# EasyEDA-Project.net
KiCad netlist of a schematic drawn in EasyEDA Pro
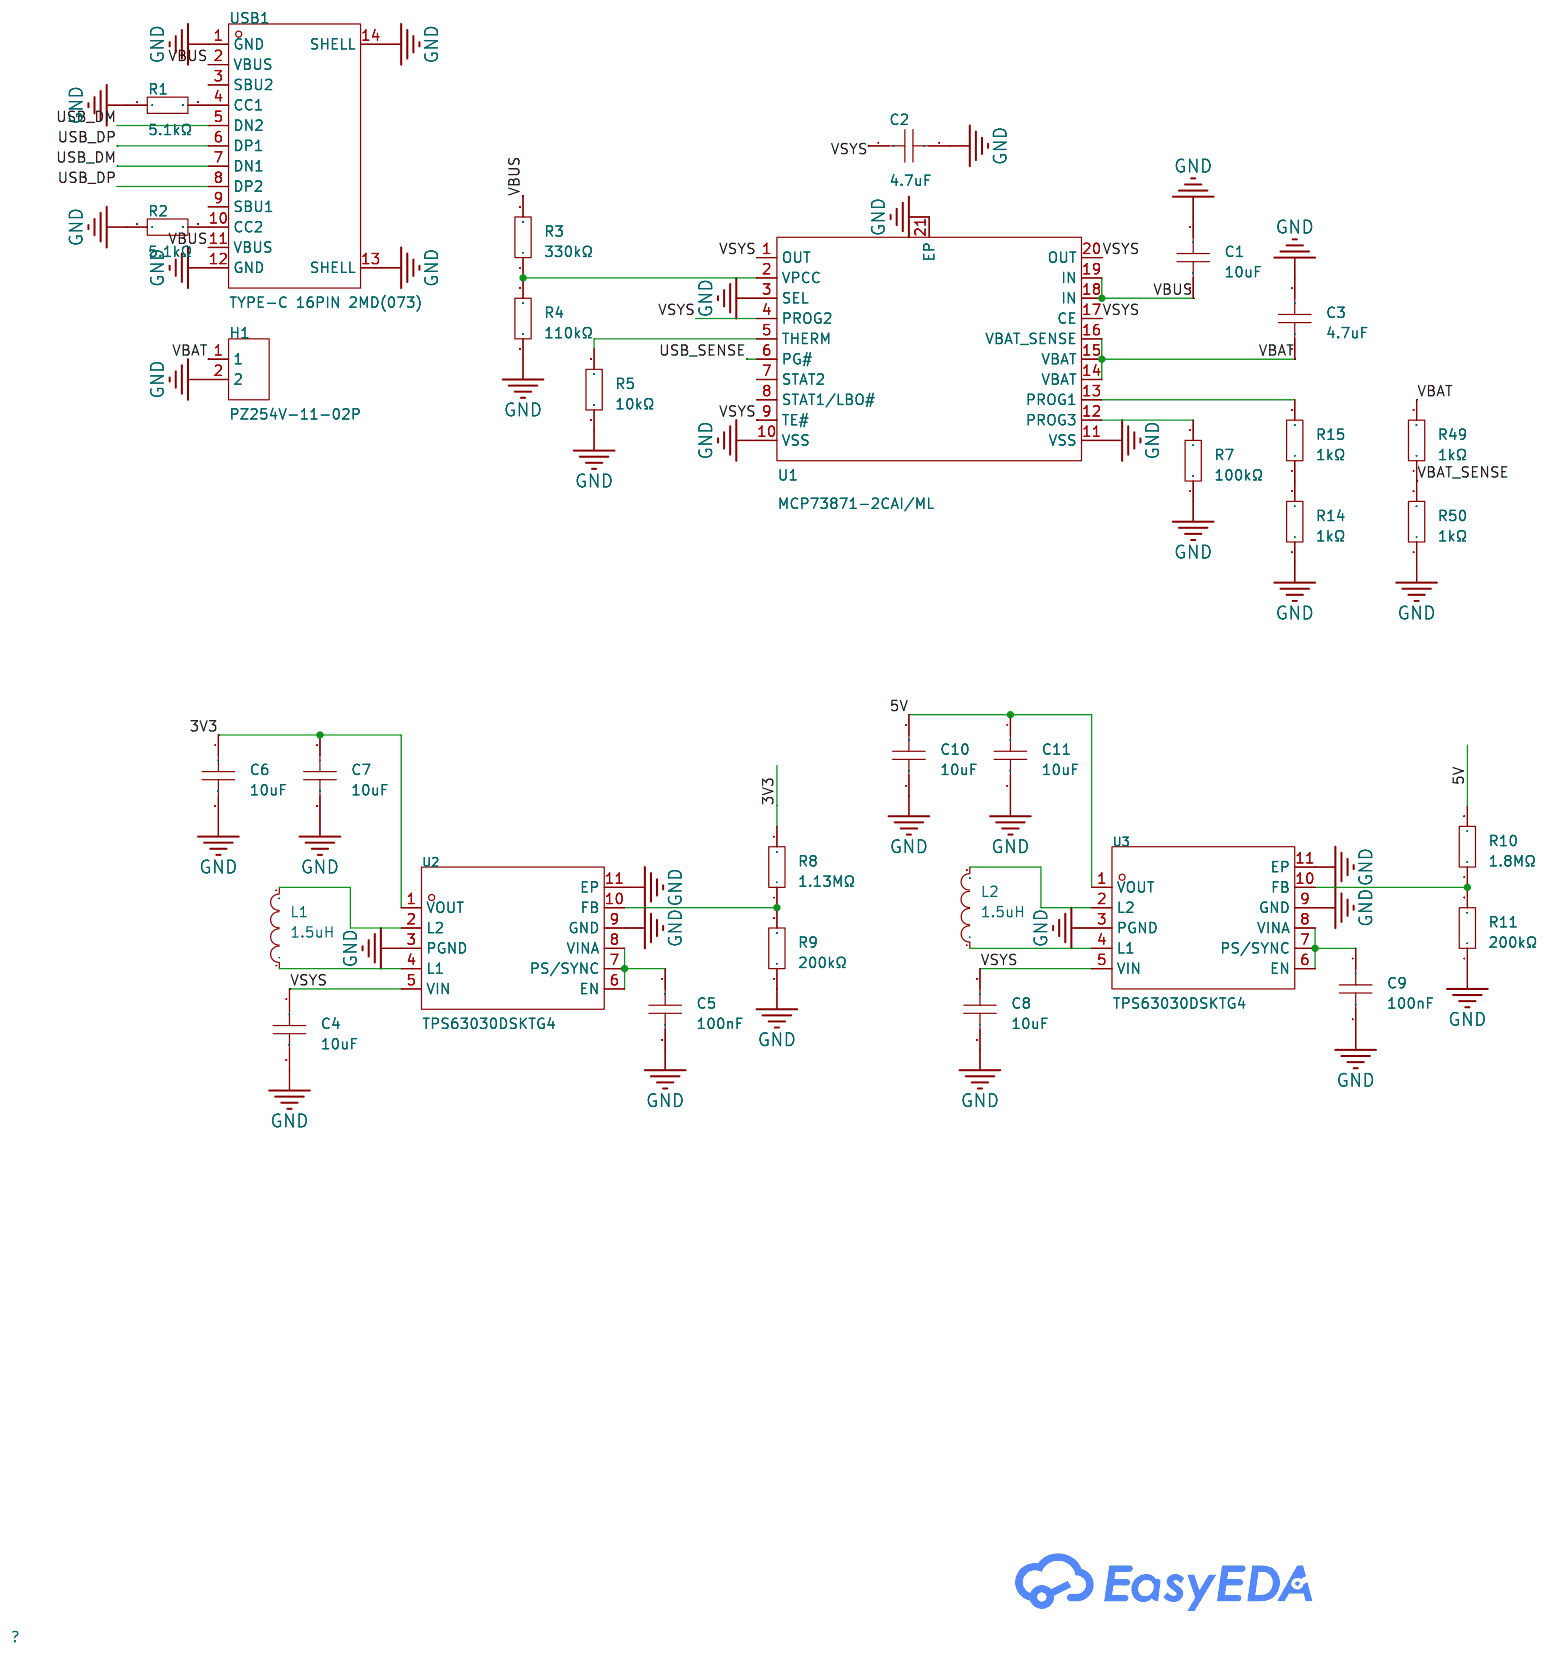
[diagram p0: Power]
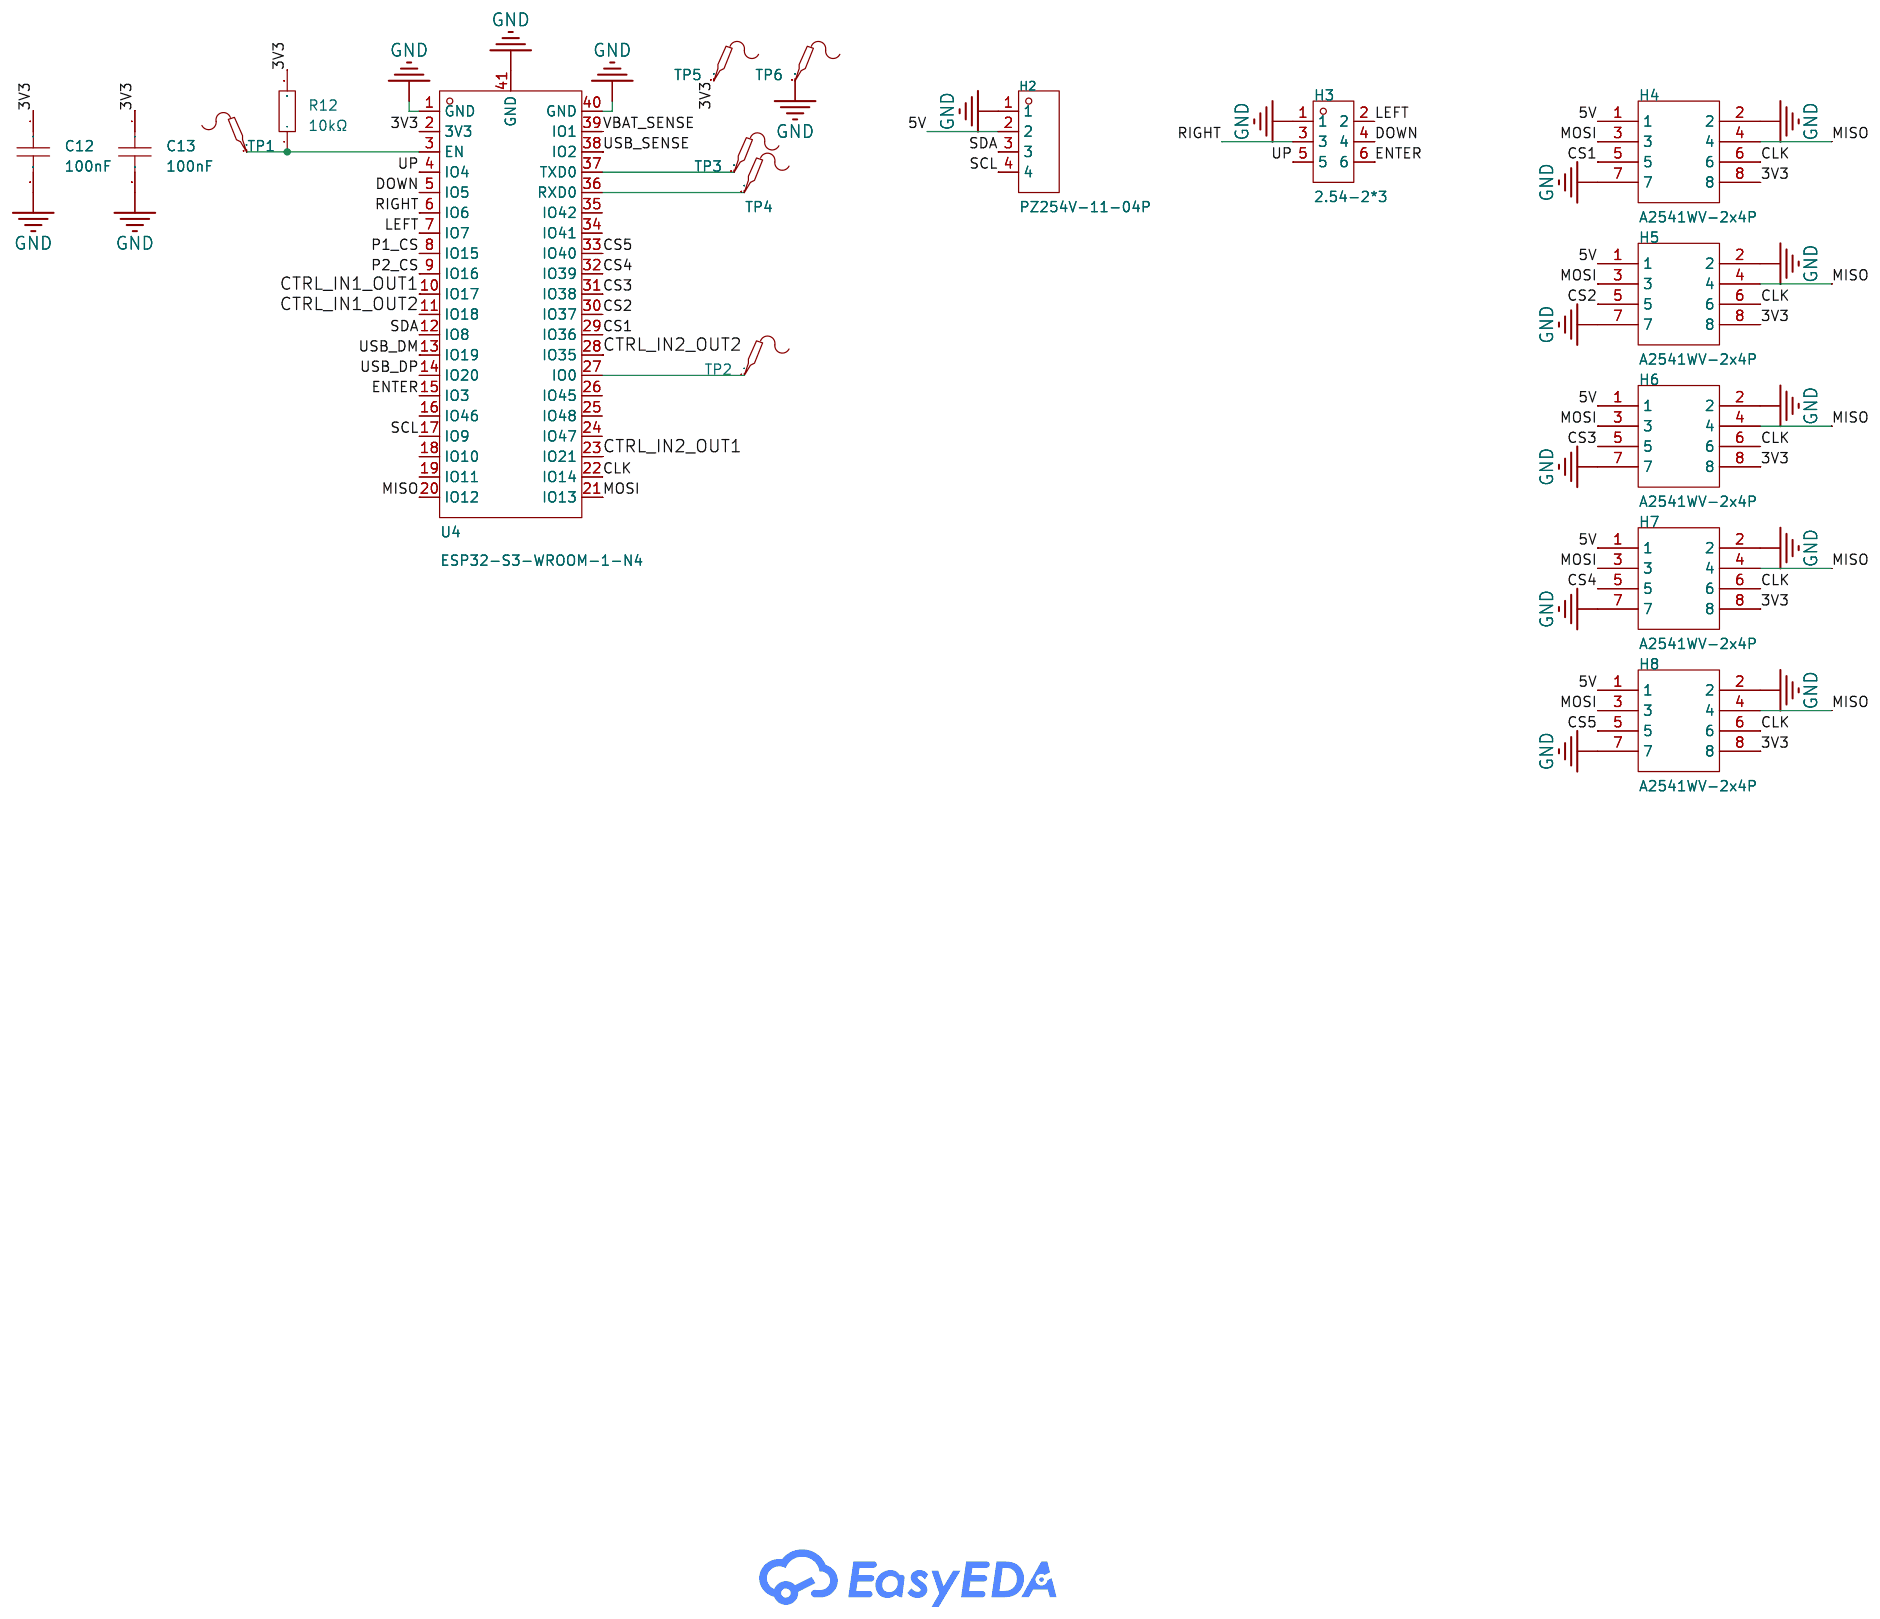
[diagram p1: MCU]
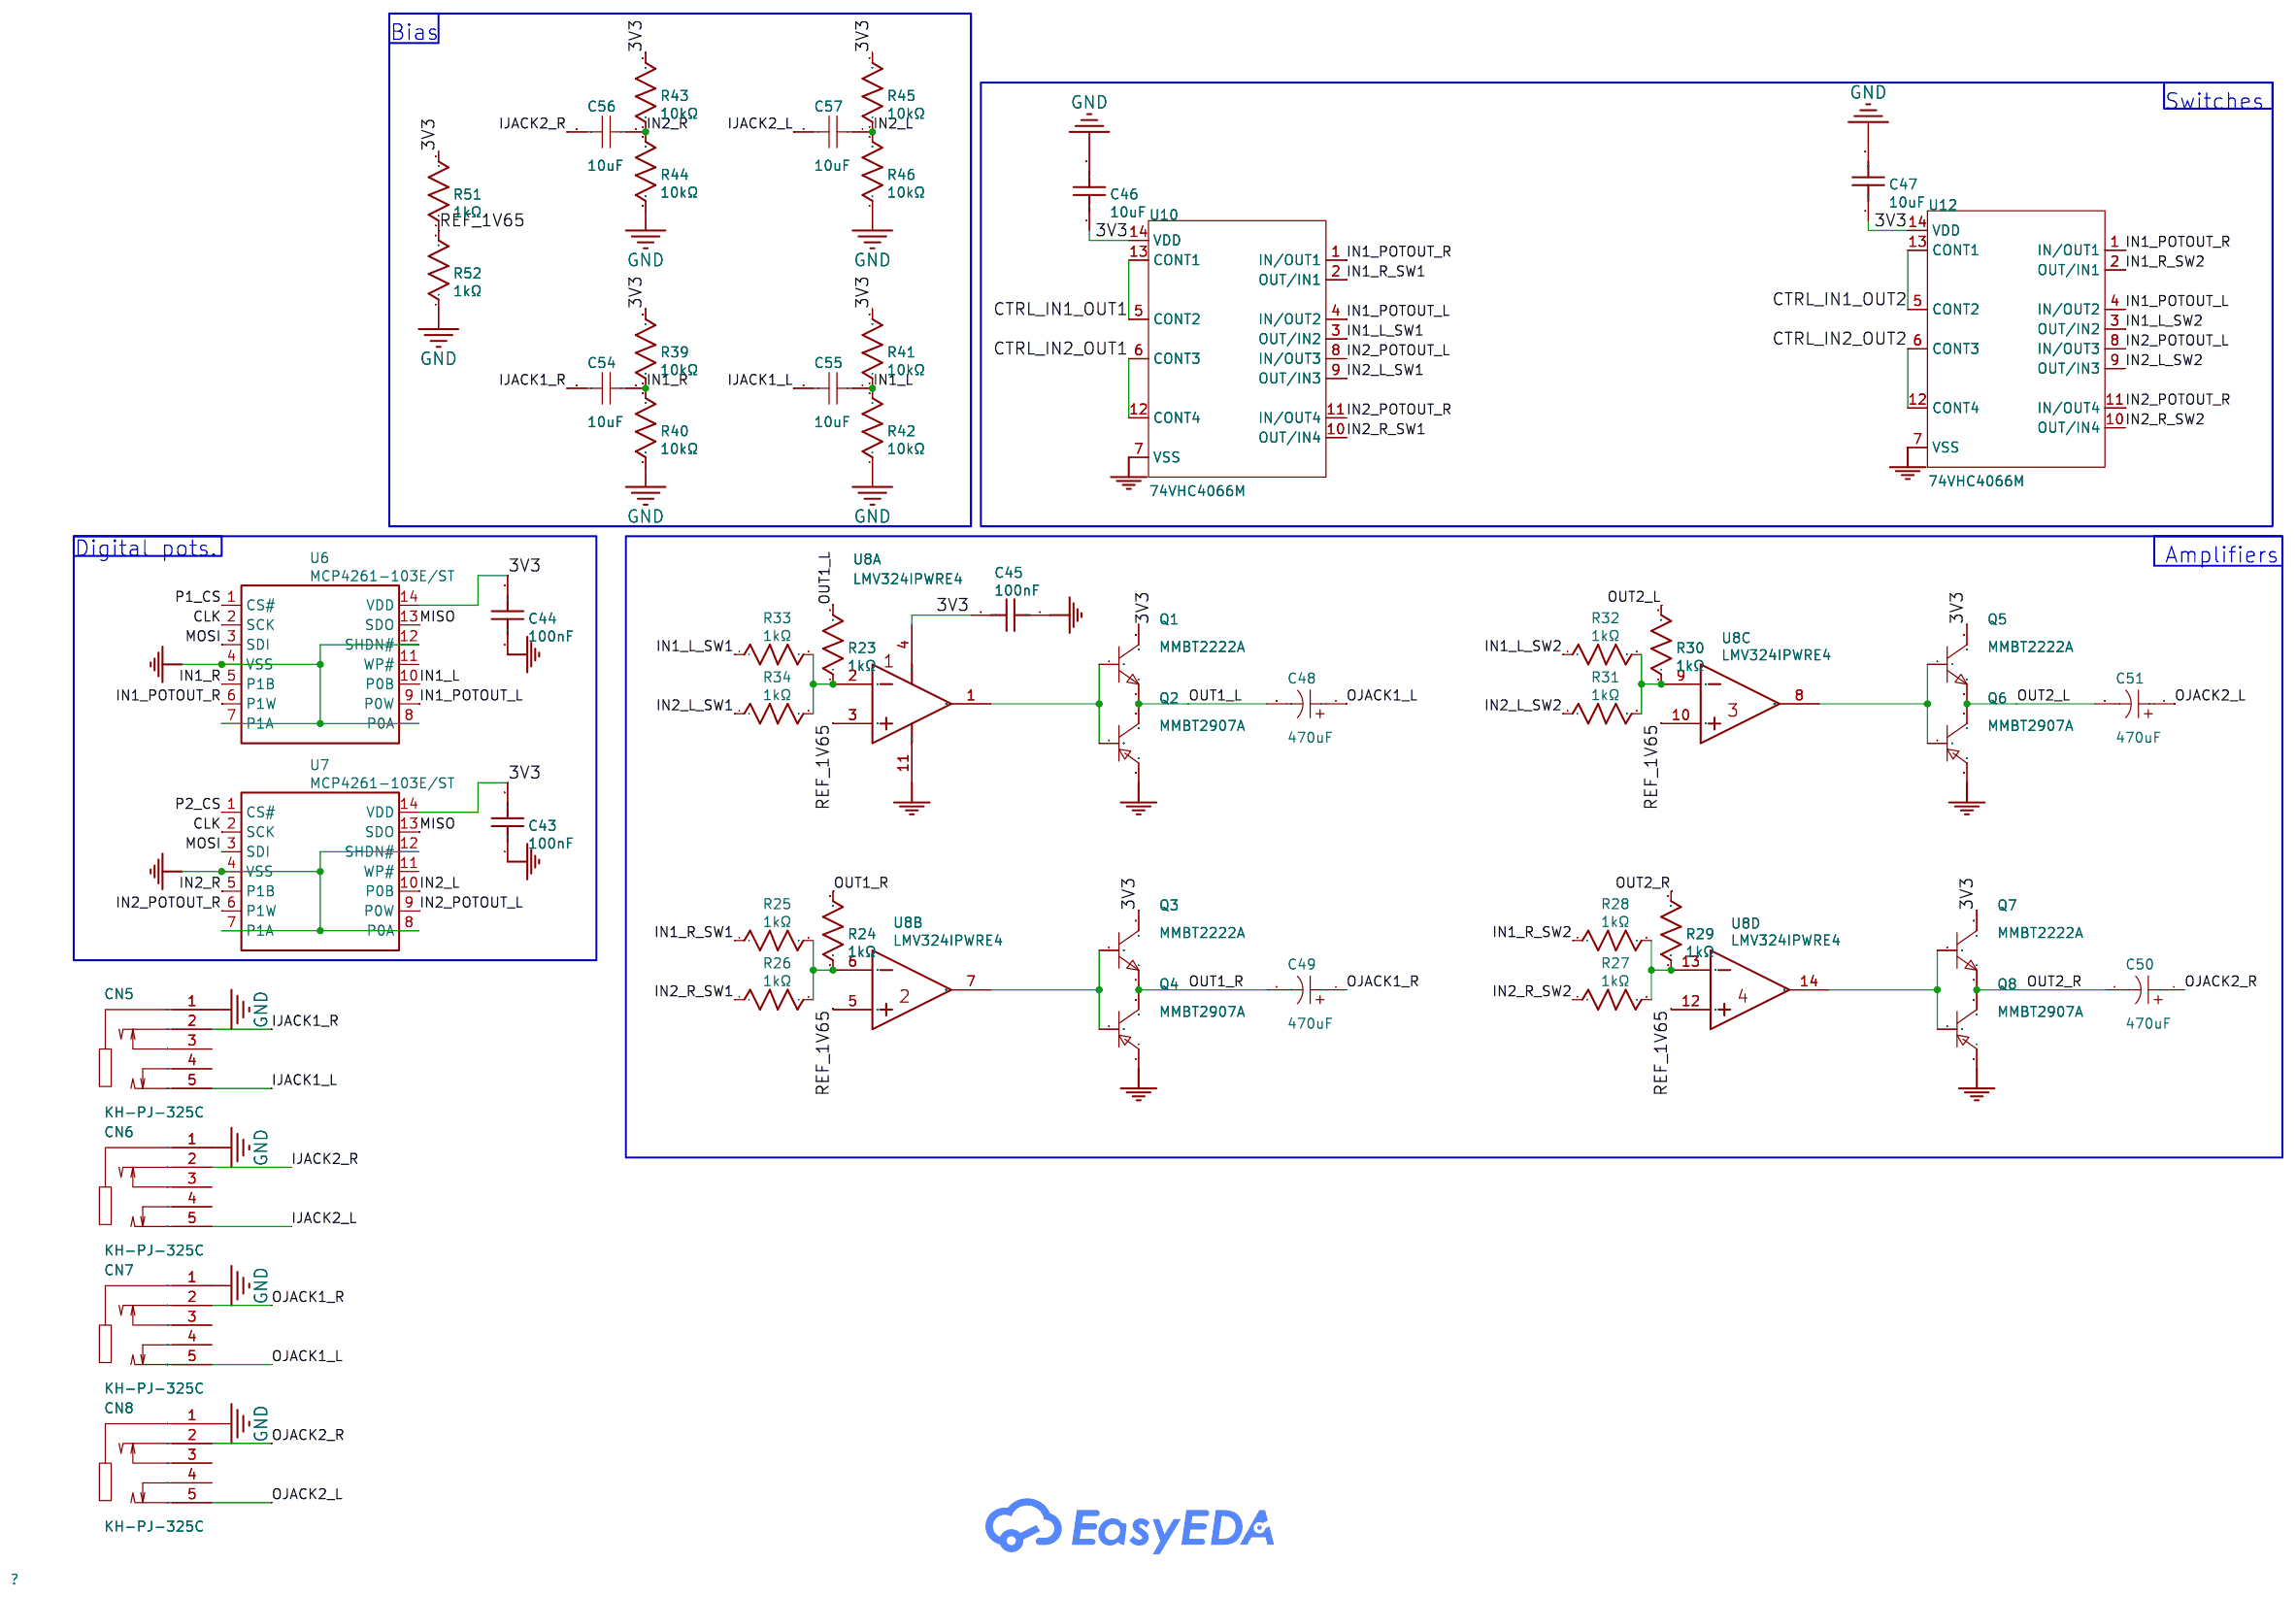
[diagram p2: Audio]

(export (version "E")
  (design (tool "Eeschema 10.0.6"))
  (components
    (comp (ref "C1")
      (value "10uF")
      (footprint "easyedapro:C0603")
      (description "Capacitance:10uF Tolerance:±20% Tolerance:±20% Voltage Rating:6.3V Temperature Coefficient:X5R")
      (fields (field (name "Manufacturer Part") "C0603B106M007T") (field (name "Manufacturer") "IHHEC(禾伸堂)"))
      (libsource (lib "easyedapro") (part "CAP"))
    )
    (comp (ref "C2")
      (value "4.7uF")
      (footprint "easyedapro:C0603")
      (description "Capacitance:4.7uF Tolerance:±10% Tolerance:±10% Voltage Rating:10V Temperature Coefficient:X5R")
      (fields
        (field (name "Manufacturer Part") "CL10A475KP8NNNC")
        (field (name "Manufacturer") "SAMSUNG(三星)")
      )
      (libsource (lib "easyedapro") (part "CAP"))
    )
    (comp (ref "C3")
      (value "4.7uF")
      (footprint "easyedapro:C0603")
      (description "Capacitance:4.7uF Tolerance:±10% Tolerance:±10% Voltage Rating:10V Temperature Coefficient:X5R")
      (fields
        (field (name "Manufacturer Part") "CL10A475KP8NNNC")
        (field (name "Manufacturer") "SAMSUNG(三星)")
      )
      (libsource (lib "easyedapro") (part "CAP"))
    )
    (comp (ref "C4")
      (value "10uF")
      (footprint "easyedapro:C0603")
      (description "Capacitance:10uF Tolerance:±20% Tolerance:±20% Voltage Rating:6.3V Temperature Coefficient:X5R")
      (fields (field (name "Manufacturer Part") "C0603B106M007T") (field (name "Manufacturer") "IHHEC(禾伸堂)"))
      (libsource (lib "easyedapro") (part "CAP"))
    )
    (comp (ref "C5")
      (value "100nF")
      (footprint "easyedapro:C0603")
      (description "Capacitance:100nF Tolerance:±10% Tolerance:±10% Voltage Rating:50V Temperature Coefficient:X7R")
      (fields
        (field (name "Manufacturer Part") "CC0603KRX7R9BB104")
        (field (name "Manufacturer") "YAGEO(国巨)")
      )
      (libsource (lib "easyedapro") (part "CAP"))
    )
    (comp (ref "C6")
      (value "10uF")
      (footprint "easyedapro:C0603")
      (description "Capacitance:10uF Tolerance:±20% Tolerance:±20% Voltage Rating:6.3V Temperature Coefficient:X5R")
      (fields (field (name "Manufacturer Part") "C0603B106M007T") (field (name "Manufacturer") "IHHEC(禾伸堂)"))
      (libsource (lib "easyedapro") (part "CAP"))
    )
    (comp (ref "C7")
      (value "10uF")
      (footprint "easyedapro:C0603")
      (description "Capacitance:10uF Tolerance:±20% Tolerance:±20% Voltage Rating:6.3V Temperature Coefficient:X5R")
      (fields (field (name "Manufacturer Part") "C0603B106M007T") (field (name "Manufacturer") "IHHEC(禾伸堂)"))
      (libsource (lib "easyedapro") (part "CAP"))
    )
    (comp (ref "C8")
      (value "10uF")
      (footprint "easyedapro:C0603")
      (description "Capacitance:10uF Tolerance:±20% Tolerance:±20% Voltage Rating:6.3V Temperature Coefficient:X5R")
      (fields (field (name "Manufacturer Part") "C0603B106M007T") (field (name "Manufacturer") "IHHEC(禾伸堂)"))
      (libsource (lib "easyedapro") (part "CAP"))
    )
    (comp (ref "C9")
      (value "100nF")
      (footprint "easyedapro:C0603")
      (description "Capacitance:100nF Tolerance:±10% Tolerance:±10% Voltage Rating:50V Temperature Coefficient:X7R")
      (fields
        (field (name "Manufacturer Part") "CC0603KRX7R9BB104")
        (field (name "Manufacturer") "YAGEO(国巨)")
      )
      (libsource (lib "easyedapro") (part "CAP"))
    )
    (comp (ref "C10")
      (value "10uF")
      (footprint "easyedapro:C0603")
      (description "Capacitance:10uF Tolerance:±20% Tolerance:±20% Voltage Rating:6.3V Temperature Coefficient:X5R")
      (fields (field (name "Manufacturer Part") "C0603B106M007T") (field (name "Manufacturer") "IHHEC(禾伸堂)"))
      (libsource (lib "easyedapro") (part "CAP"))
    )
    (comp (ref "C11")
      (value "10uF")
      (footprint "easyedapro:C0603")
      (description "Capacitance:10uF Tolerance:±20% Tolerance:±20% Voltage Rating:6.3V Temperature Coefficient:X5R")
      (fields (field (name "Manufacturer Part") "C0603B106M007T") (field (name "Manufacturer") "IHHEC(禾伸堂)"))
      (libsource (lib "easyedapro") (part "CAP"))
    )
    (comp (ref "H1")
      (value "PZ254V-11-02P")
      (footprint "easyedapro:HDR-TH_2P-P2.54-V-M")
      (fields (field (name "Manufacturer") "XFCN(兴飞)"))
      (libsource (lib "easyedapro") (part "PZ254V-11-02P"))
    )
    (comp (ref "L1")
      (value "1.5uH")
      (footprint "easyedapro:L0603")
      (fields
        (field (name "Manufacturer Part") "LB3218T1R5M")
        (field (name "Manufacturer") "TAIYO YUDEN(太诱)")
      )
      (libsource (lib "easyedapro") (part "电感"))
    )
    (comp (ref "L2")
      (value "1.5uH")
      (footprint "easyedapro:L0603")
      (fields
        (field (name "Manufacturer Part") "LB3218T1R5M")
        (field (name "Manufacturer") "TAIYO YUDEN(太诱)")
      )
      (libsource (lib "easyedapro") (part "电感"))
    )
    (comp (ref "R1")
      (value "5.1kΩ")
      (footprint "easyedapro:R0603")
      (fields
        (field (name "Manufacturer Part") "HoAR0603-1/10W-5.1KR-0.1%-TCR25")
        (field (name "Manufacturer") "Milliohm(毫欧)")
      )
      (libsource (lib "easyedapro") (part "Res"))
    )
    (comp (ref "R2")
      (value "5.1kΩ")
      (footprint "easyedapro:R0603")
      (fields
        (field (name "Manufacturer Part") "HoAR0603-1/10W-5.1KR-0.1%-TCR25")
        (field (name "Manufacturer") "Milliohm(毫欧)")
      )
      (libsource (lib "easyedapro") (part "Res"))
    )
    (comp (ref "R3")
      (value "330kΩ")
      (footprint "easyedapro:R0603")
      (fields (field (name "Manufacturer Part") "HPCR0603F330KK9") (field (name "Manufacturer") "RESI(开步睿思)"))
      (libsource (lib "easyedapro") (part "Res"))
    )
    (comp (ref "R4")
      (value "110kΩ")
      (footprint "easyedapro:R0603")
      (fields (field (name "Manufacturer Part") "PTFR0603B110KN9") (field (name "Manufacturer") "RESI(开步睿思)"))
      (libsource (lib "easyedapro") (part "Res"))
    )
    (comp (ref "R5")
      (value "10kΩ")
      (footprint "easyedapro:R0603")
      (fields (field (name "Manufacturer Part") "SCR0603J10K") (field (name "Manufacturer") "VO(翔胜)"))
      (libsource (lib "easyedapro") (part "Res"))
    )
    (comp (ref "R7")
      (value "100kΩ")
      (footprint "easyedapro:R0603")
      (fields (field (name "Manufacturer Part") "SCR0603F100K") (field (name "Manufacturer") "VO(翔胜)"))
      (libsource (lib "easyedapro") (part "Res"))
    )
    (comp (ref "R8")
      (value "1.13MΩ")
      (footprint "easyedapro:R0603")
      (fields (field (name "Manufacturer Part") "RTT031134FTP") (field (name "Manufacturer") "RALEC(旺诠)"))
      (libsource (lib "easyedapro") (part "Res"))
    )
    (comp (ref "R9")
      (value "200kΩ")
      (footprint "easyedapro:R0603")
      (fields (field (name "Manufacturer Part") "SCR0603F200K") (field (name "Manufacturer") "VO(翔胜)"))
      (libsource (lib "easyedapro") (part "Res"))
    )
    (comp (ref "R10")
      (value "1.8MΩ")
      (footprint "easyedapro:R0603")
      (fields (field (name "Manufacturer Part") "FRC0603J185TS") (field (name "Manufacturer") "FOJAN(富捷)"))
      (libsource (lib "easyedapro") (part "Res"))
    )
    (comp (ref "R11")
      (value "200kΩ")
      (footprint "easyedapro:R0603")
      (fields (field (name "Manufacturer Part") "SCR0603F200K") (field (name "Manufacturer") "VO(翔胜)"))
      (libsource (lib "easyedapro") (part "Res"))
    )
    (comp (ref "R14")
      (value "1kΩ")
      (footprint "easyedapro:R0603")
      (fields
        (field (name "Manufacturer Part") "0603WAF1001T5E")
        (field (name "Manufacturer") "UNI-ROYAL(厚声)")
      )
      (libsource (lib "easyedapro") (part "Res"))
    )
    (comp (ref "R15")
      (value "1kΩ")
      (footprint "easyedapro:R0603")
      (fields
        (field (name "Manufacturer Part") "0603WAF1001T5E")
        (field (name "Manufacturer") "UNI-ROYAL(厚声)")
      )
      (libsource (lib "easyedapro") (part "Res"))
    )
    (comp (ref "R49")
      (value "1kΩ")
      (footprint "easyedapro:R0603")
      (fields
        (field (name "Manufacturer Part") "0603WAF1001T5E")
        (field (name "Manufacturer") "UNI-ROYAL(厚声)")
      )
      (libsource (lib "easyedapro") (part "Res"))
    )
    (comp (ref "R50")
      (value "1kΩ")
      (footprint "easyedapro:R0603")
      (fields
        (field (name "Manufacturer Part") "0603WAF1001T5E")
        (field (name "Manufacturer") "UNI-ROYAL(厚声)")
      )
      (libsource (lib "easyedapro") (part "Res"))
    )
    (comp (ref "U1")
      (value "MCP73871-2CAI/ML")
      (footprint "easyedapro:QFN-20_L4.0-W4.0-P0.50-BL-EP2.7")
      (fields (field (name "Manufacturer") "MICROCHIP(美国微芯)"))
      (libsource (lib "easyedapro") (part "MCP73871-2CAI/ML"))
    )
    (comp (ref "U2")
      (value "TPS63030DSKTG4")
      (footprint "easyedapro:SON-10_L2.5-W2.5-P0.50-TL-EP")
      (fields (field (name "Manufacturer") "TI(德州仪器)"))
      (libsource (lib "easyedapro") (part "TPS63030DSKTG4"))
    )
    (comp (ref "U3")
      (value "TPS63030DSKTG4")
      (footprint "easyedapro:SON-10_L2.5-W2.5-P0.50-TL-EP")
      (fields (field (name "Manufacturer") "TI(德州仪器)"))
      (libsource (lib "easyedapro") (part "TPS63030DSKTG4"))
    )
    (comp (ref "USB1")
      (value "TYPE-C 16PIN 2MD(073)")
      (footprint "easyedapro:USB-C-SMD_TYPE-C-6PIN-2MD-073")
      (fields (field (name "Manufacturer") "SHOU HAN(首韩)"))
      (libsource (lib "easyedapro") (part "TYPE-C 16PIN 2MD(073)"))
    )
    (comp (ref "C12")
      (value "100nF")
      (footprint "easyedapro:C0603")
      (description "Capacitance:100nF Tolerance:±10% Tolerance:±10% Voltage Rating:50V Temperature Coefficient:X7R")
      (fields
        (field (name "Manufacturer Part") "CC0603KRX7R9BB104")
        (field (name "Manufacturer") "YAGEO(国巨)")
      )
      (libsource (lib "easyedapro") (part "CAP"))
    )
    (comp (ref "C13")
      (value "100nF")
      (footprint "easyedapro:C0603")
      (description "Capacitance:100nF Tolerance:±10% Tolerance:±10% Voltage Rating:50V Temperature Coefficient:X7R")
      (fields
        (field (name "Manufacturer Part") "CC0603KRX7R9BB104")
        (field (name "Manufacturer") "YAGEO(国巨)")
      )
      (libsource (lib "easyedapro") (part "CAP"))
    )
    (comp (ref "H2")
      (value "PZ254V-11-04P")
      (footprint "easyedapro:HDR-TH_4P-P2.54-V-M")
      (fields (field (name "Manufacturer") "XFCN(兴飞)"))
      (libsource (lib "easyedapro") (part "PZ254V-11-04P_C2691448"))
    )
    (comp (ref "H3")
      (value "2.54-2*3")
      (footprint "easyedapro:HDR-TH_6P-P2.54-V-R2-C3-S2.54_A2541WV-2X3P")
      (fields (field (name "Manufacturer") "ZHOURI(洲日)"))
      (libsource (lib "easyedapro") (part "2.54-2*3"))
    )
    (comp (ref "H4")
      (value "A2541WV-2x4P")
      (footprint "easyedapro:HDR-TH_8P-P2.54-V-R2-C4-S2.54_A2541WV-2X4P")
      (fields (field (name "Manufacturer") "CJT(长江连接器)"))
      (libsource (lib "easyedapro") (part "A2541WV-2X4P"))
    )
    (comp (ref "H5")
      (value "A2541WV-2x4P")
      (footprint "easyedapro:HDR-TH_8P-P2.54-V-R2-C4-S2.54_A2541WV-2X4P")
      (fields (field (name "Manufacturer") "CJT(长江连接器)"))
      (libsource (lib "easyedapro") (part "A2541WV-2X4P"))
    )
    (comp (ref "H6")
      (value "A2541WV-2x4P")
      (footprint "easyedapro:HDR-TH_8P-P2.54-V-R2-C4-S2.54_A2541WV-2X4P")
      (fields (field (name "Manufacturer") "CJT(长江连接器)"))
      (libsource (lib "easyedapro") (part "A2541WV-2X4P"))
    )
    (comp (ref "H7")
      (value "A2541WV-2x4P")
      (footprint "easyedapro:HDR-TH_8P-P2.54-V-R2-C4-S2.54_A2541WV-2X4P")
      (fields (field (name "Manufacturer") "CJT(长江连接器)"))
      (libsource (lib "easyedapro") (part "A2541WV-2X4P"))
    )
    (comp (ref "H8")
      (value "A2541WV-2x4P")
      (footprint "easyedapro:HDR-TH_8P-P2.54-V-R2-C4-S2.54_A2541WV-2X4P")
      (fields (field (name "Manufacturer") "CJT(长江连接器)"))
      (libsource (lib "easyedapro") (part "A2541WV-2X4P"))
    )
    (comp (ref "R12")
      (value "10kΩ")
      (footprint "easyedapro:R0603")
      (fields (field (name "Manufacturer Part") "SCR0603J10K") (field (name "Manufacturer") "VO(翔胜)"))
      (libsource (lib "easyedapro") (part "Res"))
    )
    (comp (ref "TP1")
      (value "~")
      (footprint "easyedapro:Test-Point-0.5mm")
      (description "Test Point 测试点")
      (libsource (lib "easyedapro") (part "Test-Point"))
    )
    (comp (ref "TP2")
      (value "~")
      (footprint "easyedapro:Test-Point-0.5mm")
      (description "Test Point 测试点")
      (libsource (lib "easyedapro") (part "Test-Point"))
    )
    (comp (ref "TP3")
      (value "~")
      (footprint "easyedapro:Test-Point-0.5mm")
      (description "Test Point 测试点")
      (libsource (lib "easyedapro") (part "Test-Point"))
    )
    (comp (ref "TP4")
      (value "~")
      (footprint "easyedapro:Test-Point-0.5mm")
      (description "Test Point 测试点")
      (libsource (lib "easyedapro") (part "Test-Point"))
    )
    (comp (ref "TP5")
      (value "~")
      (footprint "easyedapro:Test-Point-0.5mm")
      (description "Test Point 测试点")
      (libsource (lib "easyedapro") (part "Test-Point"))
    )
    (comp (ref "TP6")
      (value "~")
      (footprint "easyedapro:Test-Point-0.5mm")
      (description "Test Point 测试点")
      (libsource (lib "easyedapro") (part "Test-Point"))
    )
    (comp (ref "U4")
      (value "ESP32-S3-WROOM-1-N4")
      (footprint "easyedapro:WIFIM-SMD_ESP32-S3-WROOM-1-N8")
      (fields (field (name "Manufacturer") "ESPRESSIF(乐鑫)"))
      (libsource (lib "easyedapro") (part "ESP32-S3-WROOM-1-N4"))
    )
    (comp (ref "C43")
      (value "100nF")
      (footprint "easyedapro:C0603")
      (description "Capacitance:100nF Tolerance:±10% Tolerance:±10% Voltage Rating:50V Temperature Coefficient:X7R")
      (fields (field (name "Manufacturer") "YAGEO(国巨)"))
      (libsource (lib "easyedapro") (part "0.1u"))
    )
    (comp (ref "C44")
      (value "100nF")
      (footprint "easyedapro:C0603")
      (description "Capacitance:100nF Tolerance:±10% Tolerance:±10% Voltage Rating:50V Temperature Coefficient:X7R")
      (fields (field (name "Manufacturer") "YAGEO(国巨)"))
      (libsource (lib "easyedapro") (part "0.1u"))
    )
    (comp (ref "C45")
      (value "100nF")
      (footprint "easyedapro:C0603")
      (description "Capacitance:100nF Tolerance:±10% Tolerance:±10% Voltage Rating:50V Temperature Coefficient:X7R")
      (fields (field (name "Manufacturer") "YAGEO(国巨)"))
      (libsource (lib "easyedapro") (part "0.1u"))
    )
    (comp (ref "C46")
      (value "10uF")
      (footprint "easyedapro:C0603")
      (description "Capacitance:10uF Tolerance:±20% Tolerance:±20% Voltage Rating:6.3V Temperature Coefficient:X5R")
      (fields (field (name "Manufacturer") "IHHEC(禾伸堂)"))
      (libsource (lib "easyedapro") (part "10uF"))
    )
    (comp (ref "C47")
      (value "10uF")
      (footprint "easyedapro:C0603")
      (description "Capacitance:10uF Tolerance:±20% Tolerance:±20% Voltage Rating:6.3V Temperature Coefficient:X5R")
      (fields (field (name "Manufacturer") "IHHEC(禾伸堂)"))
      (libsource (lib "easyedapro") (part "10uF"))
    )
    (comp (ref "C48")
      (value "470uF")
      (footprint "easyedapro:CAP-SMD_L7.3-W4.3-FD")
      (fields
        (field (name "Manufacturer Part") "CA45-D-6.3V-470UF-K")
        (field (name "Manufacturer") "CEC(振华新云)")
      )
      (libsource (lib "easyedapro") (part "CA45-D-6.3V-470UF-K"))
    )
    (comp (ref "C49")
      (value "470uF")
      (footprint "easyedapro:CAP-SMD_L7.3-W4.3-FD")
      (fields
        (field (name "Manufacturer Part") "CA45-D-6.3V-470UF-K")
        (field (name "Manufacturer") "CEC(振华新云)")
      )
      (libsource (lib "easyedapro") (part "CA45-D-6.3V-470UF-K"))
    )
    (comp (ref "C50")
      (value "470uF")
      (footprint "easyedapro:CAP-SMD_L7.3-W4.3-FD")
      (fields
        (field (name "Manufacturer Part") "CA45-D-6.3V-470UF-K")
        (field (name "Manufacturer") "CEC(振华新云)")
      )
      (libsource (lib "easyedapro") (part "CA45-D-6.3V-470UF-K"))
    )
    (comp (ref "C51")
      (value "470uF")
      (footprint "easyedapro:CAP-SMD_L7.3-W4.3-FD")
      (fields
        (field (name "Manufacturer Part") "CA45-D-6.3V-470UF-K")
        (field (name "Manufacturer") "CEC(振华新云)")
      )
      (libsource (lib "easyedapro") (part "CA45-D-6.3V-470UF-K"))
    )
    (comp (ref "C54")
      (value "10uF")
      (footprint "easyedapro:C0603")
      (description "Capacitance:10uF Tolerance:±20% Tolerance:±20% Voltage Rating:6.3V Temperature Coefficient:X5R")
      (fields (field (name "Manufacturer Part") "C0603B106M007T") (field (name "Manufacturer") "IHHEC(禾伸堂)"))
      (libsource (lib "easyedapro") (part "CAP"))
    )
    (comp (ref "C55")
      (value "10uF")
      (footprint "easyedapro:C0603")
      (description "Capacitance:10uF Tolerance:±20% Tolerance:±20% Voltage Rating:6.3V Temperature Coefficient:X5R")
      (fields (field (name "Manufacturer Part") "C0603B106M007T") (field (name "Manufacturer") "IHHEC(禾伸堂)"))
      (libsource (lib "easyedapro") (part "CAP"))
    )
    (comp (ref "C56")
      (value "10uF")
      (footprint "easyedapro:C0603")
      (description "Capacitance:10uF Tolerance:±20% Tolerance:±20% Voltage Rating:6.3V Temperature Coefficient:X5R")
      (fields (field (name "Manufacturer Part") "C0603B106M007T") (field (name "Manufacturer") "IHHEC(禾伸堂)"))
      (libsource (lib "easyedapro") (part "CAP"))
    )
    (comp (ref "C57")
      (value "10uF")
      (footprint "easyedapro:C0603")
      (description "Capacitance:10uF Tolerance:±20% Tolerance:±20% Voltage Rating:6.3V Temperature Coefficient:X5R")
      (fields (field (name "Manufacturer Part") "C0603B106M007T") (field (name "Manufacturer") "IHHEC(禾伸堂)"))
      (libsource (lib "easyedapro") (part "CAP"))
    )
    (comp (ref "CN5")
      (value "KH-PJ-325C")
      (footprint "easyedapro:AUDIO-TH_KH-PJ-325C")
      (description "Connector Type:3.5mm Headphone Jack Contact Material:Brass；Bronze Contact Plating:Gold；Tin")
      (fields (field (name "Manufacturer") "kinghelm(金航标)"))
      (libsource (lib "easyedapro") (part "KH-PJ-325C"))
    )
    (comp (ref "CN6")
      (value "KH-PJ-325C")
      (footprint "easyedapro:AUDIO-TH_KH-PJ-325C")
      (description "Connector Type:3.5mm Headphone Jack Contact Material:Brass；Bronze Contact Plating:Gold；Tin")
      (fields (field (name "Manufacturer") "kinghelm(金航标)"))
      (libsource (lib "easyedapro") (part "KH-PJ-325C"))
    )
    (comp (ref "CN7")
      (value "KH-PJ-325C")
      (footprint "easyedapro:AUDIO-TH_KH-PJ-325C")
      (description "Connector Type:3.5mm Headphone Jack Contact Material:Brass；Bronze Contact Plating:Gold；Tin")
      (fields (field (name "Manufacturer") "kinghelm(金航标)"))
      (libsource (lib "easyedapro") (part "KH-PJ-325C"))
    )
    (comp (ref "CN8")
      (value "KH-PJ-325C")
      (footprint "easyedapro:AUDIO-TH_KH-PJ-325C")
      (description "Connector Type:3.5mm Headphone Jack Contact Material:Brass；Bronze Contact Plating:Gold；Tin")
      (fields (field (name "Manufacturer") "kinghelm(金航标)"))
      (libsource (lib "easyedapro") (part "KH-PJ-325C"))
    )
    (comp (ref "Q1")
      (value "MMBT2222A")
      (footprint "easyedapro:SOT-23-3_L2.9-W1.6-P1.90-LS2.8-BR")
      (fields (field (name "Manufacturer") "TDSEMIC(拓电半导体)"))
      (libsource (lib "easyedapro") (part "MMBT2222A_C42441802"))
    )
    (comp (ref "Q2")
      (value "MMBT2907A")
      (footprint "easyedapro:SOT-23-3_L2.9-W1.3-P1.90-LS2.4-BR")
      (fields (field (name "Manufacturer") "R+O(宏嘉诚)"))
      (libsource (lib "easyedapro") (part "MMBT2907A_C7420352"))
    )
    (comp (ref "Q3")
      (value "MMBT2222A")
      (footprint "easyedapro:SOT-23-3_L2.9-W1.6-P1.90-LS2.8-BR")
      (fields (field (name "Manufacturer") "TDSEMIC(拓电半导体)"))
      (libsource (lib "easyedapro") (part "MMBT2222A_C42441802"))
    )
    (comp (ref "Q4")
      (value "MMBT2907A")
      (footprint "easyedapro:SOT-23-3_L2.9-W1.3-P1.90-LS2.4-BR")
      (fields (field (name "Manufacturer") "R+O(宏嘉诚)"))
      (libsource (lib "easyedapro") (part "MMBT2907A_C7420352"))
    )
    (comp (ref "Q5")
      (value "MMBT2222A")
      (footprint "easyedapro:SOT-23-3_L2.9-W1.6-P1.90-LS2.8-BR")
      (fields (field (name "Manufacturer") "TDSEMIC(拓电半导体)"))
      (libsource (lib "easyedapro") (part "MMBT2222A_C42441802"))
    )
    (comp (ref "Q6")
      (value "MMBT2907A")
      (footprint "easyedapro:SOT-23-3_L2.9-W1.3-P1.90-LS2.4-BR")
      (fields (field (name "Manufacturer") "R+O(宏嘉诚)"))
      (libsource (lib "easyedapro") (part "MMBT2907A_C7420352"))
    )
    (comp (ref "Q7")
      (value "MMBT2222A")
      (footprint "easyedapro:SOT-23-3_L2.9-W1.6-P1.90-LS2.8-BR")
      (fields (field (name "Manufacturer") "TDSEMIC(拓电半导体)"))
      (libsource (lib "easyedapro") (part "MMBT2222A_C42441802"))
    )
    (comp (ref "Q8")
      (value "MMBT2907A")
      (footprint "easyedapro:SOT-23-3_L2.9-W1.3-P1.90-LS2.4-BR")
      (fields (field (name "Manufacturer") "R+O(宏嘉诚)"))
      (libsource (lib "easyedapro") (part "MMBT2907A_C7420352"))
    )
    (comp (ref "R23")
      (value "1kΩ")
      (footprint "easyedapro:R0603")
      (fields (field (name "Manufacturer") "UNI-ROYAL(厚声)"))
      (libsource (lib "easyedapro") (part "1k"))
    )
    (comp (ref "R24")
      (value "1kΩ")
      (footprint "easyedapro:R0603")
      (fields (field (name "Manufacturer") "UNI-ROYAL(厚声)"))
      (libsource (lib "easyedapro") (part "1k"))
    )
    (comp (ref "R25")
      (value "1kΩ")
      (footprint "easyedapro:R0603")
      (fields (field (name "Manufacturer") "UNI-ROYAL(厚声)"))
      (libsource (lib "easyedapro") (part "1k"))
    )
    (comp (ref "R26")
      (value "1kΩ")
      (footprint "easyedapro:R0603")
      (fields (field (name "Manufacturer") "UNI-ROYAL(厚声)"))
      (libsource (lib "easyedapro") (part "1k"))
    )
    (comp (ref "R27")
      (value "1kΩ")
      (footprint "easyedapro:R0603")
      (fields (field (name "Manufacturer") "UNI-ROYAL(厚声)"))
      (libsource (lib "easyedapro") (part "1k"))
    )
    (comp (ref "R28")
      (value "1kΩ")
      (footprint "easyedapro:R0603")
      (fields (field (name "Manufacturer") "UNI-ROYAL(厚声)"))
      (libsource (lib "easyedapro") (part "1k"))
    )
    (comp (ref "R29")
      (value "1kΩ")
      (footprint "easyedapro:R0603")
      (fields (field (name "Manufacturer") "UNI-ROYAL(厚声)"))
      (libsource (lib "easyedapro") (part "1k"))
    )
    (comp (ref "R30")
      (value "1kΩ")
      (footprint "easyedapro:R0603")
      (fields (field (name "Manufacturer") "UNI-ROYAL(厚声)"))
      (libsource (lib "easyedapro") (part "1k"))
    )
    (comp (ref "R31")
      (value "1kΩ")
      (footprint "easyedapro:R0603")
      (fields (field (name "Manufacturer") "UNI-ROYAL(厚声)"))
      (libsource (lib "easyedapro") (part "1k"))
    )
    (comp (ref "R32")
      (value "1kΩ")
      (footprint "easyedapro:R0603")
      (fields (field (name "Manufacturer") "UNI-ROYAL(厚声)"))
      (libsource (lib "easyedapro") (part "1k"))
    )
    (comp (ref "R33")
      (value "1kΩ")
      (footprint "easyedapro:R0603")
      (fields (field (name "Manufacturer") "UNI-ROYAL(厚声)"))
      (libsource (lib "easyedapro") (part "1k"))
    )
    (comp (ref "R34")
      (value "1kΩ")
      (footprint "easyedapro:R0603")
      (fields (field (name "Manufacturer") "UNI-ROYAL(厚声)"))
      (libsource (lib "easyedapro") (part "1k"))
    )
    (comp (ref "R39")
      (value "10kΩ")
      (footprint "easyedapro:R0603")
      (fields (field (name "Manufacturer") "VO(翔胜)"))
      (libsource (lib "easyedapro") (part "1k"))
    )
    (comp (ref "R40")
      (value "10kΩ")
      (footprint "easyedapro:R0603")
      (fields (field (name "Manufacturer") "VO(翔胜)"))
      (libsource (lib "easyedapro") (part "1k"))
    )
    (comp (ref "R41")
      (value "10kΩ")
      (footprint "easyedapro:R0603")
      (fields (field (name "Manufacturer") "VO(翔胜)"))
      (libsource (lib "easyedapro") (part "1k"))
    )
    (comp (ref "R42")
      (value "10kΩ")
      (footprint "easyedapro:R0603")
      (fields (field (name "Manufacturer") "VO(翔胜)"))
      (libsource (lib "easyedapro") (part "1k"))
    )
    (comp (ref "R43")
      (value "10kΩ")
      (footprint "easyedapro:R0603")
      (fields (field (name "Manufacturer") "VO(翔胜)"))
      (libsource (lib "easyedapro") (part "1k"))
    )
    (comp (ref "R44")
      (value "10kΩ")
      (footprint "easyedapro:R0603")
      (fields (field (name "Manufacturer") "VO(翔胜)"))
      (libsource (lib "easyedapro") (part "1k"))
    )
    (comp (ref "R45")
      (value "10kΩ")
      (footprint "easyedapro:R0603")
      (fields (field (name "Manufacturer") "VO(翔胜)"))
      (libsource (lib "easyedapro") (part "1k"))
    )
    (comp (ref "R46")
      (value "10kΩ")
      (footprint "easyedapro:R0603")
      (fields (field (name "Manufacturer") "VO(翔胜)"))
      (libsource (lib "easyedapro") (part "1k"))
    )
    (comp (ref "R51")
      (value "1kΩ")
      (footprint "easyedapro:R0603")
      (fields (field (name "Manufacturer") "UNI-ROYAL(厚声)"))
      (libsource (lib "easyedapro") (part "1k"))
    )
    (comp (ref "R52")
      (value "1kΩ")
      (footprint "easyedapro:R0603")
      (fields (field (name "Manufacturer") "UNI-ROYAL(厚声)"))
      (libsource (lib "easyedapro") (part "1k"))
    )
    (comp (ref "U6")
      (value "MCP4261-103E/ST")
      (footprint "easyedapro:TSSOP-14_L5.0-W4.4-P0.65-LS6.4-BL")
      (fields (field (name "Manufacturer") "MICROCHIP(美国微芯)") (field (name "Contributor") "LCSC"))
      (libsource (lib "easyedapro") (part "MCP4261-103E/ST"))
    )
    (comp (ref "U7")
      (value "MCP4261-103E/ST")
      (footprint "easyedapro:TSSOP-14_L5.0-W4.4-P0.65-LS6.4-BL")
      (fields (field (name "Manufacturer") "MICROCHIP(美国微芯)") (field (name "Contributor") "LCSC"))
      (libsource (lib "easyedapro") (part "MCP4261-103E/ST"))
    )
    (comp (ref "U8")
      (value "LMV324IPWRE4")
      (footprint "easyedapro:TSSOP-14_L5.0-W4.4-P0.65-LS6.4-BL")
      (fields (field (name "Manufacturer") "TI(德州仪器)") (field (name "subpart_no") "1"))
      (libsource (lib "easyedapro") (part "LMV324IPWRE4"))
    )
    (comp (ref "U10")
      (value "74VHC4066M")
      (footprint "easyedapro:PDIP-14_L19.7-W6.6-P2.54-LS8.3-BL")
      (fields (field (name "Manufacturer") "onsemi(安森美)"))
      (libsource (lib "easyedapro") (part "74VHC4066N"))
    )
    (comp (ref "U12")
      (value "74VHC4066M")
      (footprint "easyedapro:PDIP-14_L19.7-W6.6-P2.54-LS8.3-BL")
      (fields (field (name "Manufacturer") "onsemi(安森美)"))
      (libsource (lib "easyedapro") (part "74VHC4066N"))
    )
  )
  (nets
    (net (code "1") (name "3V3") (class "Default")
      (node (ref "C12") (pin "1") (pinfunction "1_1") (pintype "input"))
      (node (ref "C13") (pin "1") (pinfunction "1_1") (pintype "input"))
      (node (ref "C43") (pin "2") (pinfunction "2_2") (pintype "unspecified"))
      (node (ref "C44") (pin "2") (pinfunction "2_2") (pintype "unspecified"))
      (node (ref "C45") (pin "2") (pinfunction "2_2") (pintype "unspecified"))
      (node (ref "C46") (pin "1") (pinfunction "1_1") (pintype "unspecified"))
      (node (ref "C47") (pin "1") (pinfunction "1_1") (pintype "unspecified"))
      (node (ref "C6") (pin "1") (pinfunction "1_1") (pintype "input"))
      (node (ref "C7") (pin "1") (pinfunction "1_1") (pintype "input"))
      (node (ref "H4") (pin "8") (pinfunction "8_8") (pintype "unspecified"))
      (node (ref "H5") (pin "8") (pinfunction "8_8") (pintype "unspecified"))
      (node (ref "H6") (pin "8") (pinfunction "8_8") (pintype "unspecified"))
      (node (ref "H7") (pin "8") (pinfunction "8_8") (pintype "unspecified"))
      (node (ref "H8") (pin "8") (pinfunction "8_8") (pintype "unspecified"))
      (node (ref "Q1") (pin "3") (pinfunction "C_3") (pintype "input"))
      (node (ref "Q3") (pin "3") (pinfunction "C_3") (pintype "input"))
      (node (ref "Q5") (pin "3") (pinfunction "C_3") (pintype "input"))
      (node (ref "Q7") (pin "3") (pinfunction "C_3") (pintype "input"))
      (node (ref "R12") (pin "2") (pinfunction "2_2") (pintype "input"))
      (node (ref "R39") (pin "2") (pinfunction "2_2") (pintype "unspecified"))
      (node (ref "R41") (pin "2") (pinfunction "2_2") (pintype "unspecified"))
      (node (ref "R43") (pin "2") (pinfunction "2_2") (pintype "unspecified"))
      (node (ref "R45") (pin "2") (pinfunction "2_2") (pintype "unspecified"))
      (node (ref "R51") (pin "2") (pinfunction "2_2") (pintype "unspecified"))
      (node (ref "R8") (pin "2") (pinfunction "2_2") (pintype "input"))
      (node (ref "TP5") (pin "1") (pinfunction "1_1") (pintype "unspecified"))
      (node (ref "U10") (pin "14") (pinfunction "VDD_14") (pintype "unspecified"))
      (node (ref "U12") (pin "14") (pinfunction "VDD_14") (pintype "unspecified"))
      (node (ref "U2") (pin "1") (pinfunction "VOUT_1") (pintype "input"))
      (node (ref "U4") (pin "2") (pinfunction "3V3_2") (pintype "unspecified"))
      (node (ref "U6") (pin "14") (pinfunction "VDD_14") (pintype "unspecified"))
      (node (ref "U7") (pin "14") (pinfunction "VDD_14") (pintype "unspecified"))
      (node (ref "U8") (pin "4") (pinfunction "VCC+_4") (pintype "unspecified"))
    )
    (net (code "2") (name "5V") (class "Default")
      (node (ref "C10") (pin "1") (pinfunction "1_1") (pintype "input"))
      (node (ref "C11") (pin "1") (pinfunction "1_1") (pintype "input"))
      (node (ref "H2") (pin "2") (pinfunction "2_2") (pintype "input"))
      (node (ref "H4") (pin "1") (pinfunction "1_1") (pintype "unspecified"))
      (node (ref "H5") (pin "1") (pinfunction "1_1") (pintype "unspecified"))
      (node (ref "H6") (pin "1") (pinfunction "1_1") (pintype "unspecified"))
      (node (ref "H7") (pin "1") (pinfunction "1_1") (pintype "unspecified"))
      (node (ref "H8") (pin "1") (pinfunction "1_1") (pintype "unspecified"))
      (node (ref "R10") (pin "2") (pinfunction "2_2") (pintype "input"))
      (node (ref "U3") (pin "1") (pinfunction "VOUT_1") (pintype "input"))
    )
    (net (code "3") (name "CLK") (class "Default")
      (node (ref "H4") (pin "6") (pinfunction "6_6") (pintype "unspecified"))
      (node (ref "H5") (pin "6") (pinfunction "6_6") (pintype "unspecified"))
      (node (ref "H6") (pin "6") (pinfunction "6_6") (pintype "unspecified"))
      (node (ref "H7") (pin "6") (pinfunction "6_6") (pintype "unspecified"))
      (node (ref "H8") (pin "6") (pinfunction "6_6") (pintype "unspecified"))
      (node (ref "U4") (pin "22") (pinfunction "IO14_22") (pintype "unspecified"))
      (node (ref "U6") (pin "2") (pinfunction "SCK_2") (pintype "unspecified"))
      (node (ref "U7") (pin "2") (pinfunction "SCK_2") (pintype "unspecified"))
    )
    (net (code "4") (name "CS1") (class "Default")
      (node (ref "H4") (pin "5") (pinfunction "5_5") (pintype "unspecified"))
      (node (ref "U4") (pin "29") (pinfunction "IO36_29") (pintype "unspecified"))
    )
    (net (code "5") (name "CS2") (class "Default")
      (node (ref "H5") (pin "5") (pinfunction "5_5") (pintype "unspecified"))
      (node (ref "U4") (pin "30") (pinfunction "IO37_30") (pintype "unspecified"))
    )
    (net (code "6") (name "CS3") (class "Default")
      (node (ref "H6") (pin "5") (pinfunction "5_5") (pintype "unspecified"))
      (node (ref "U4") (pin "31") (pinfunction "IO38_31") (pintype "unspecified"))
    )
    (net (code "7") (name "CS4") (class "Default")
      (node (ref "H7") (pin "5") (pinfunction "5_5") (pintype "unspecified"))
      (node (ref "U4") (pin "32") (pinfunction "IO39_32") (pintype "unspecified"))
    )
    (net (code "8") (name "CS5") (class "Default")
      (node (ref "H8") (pin "5") (pinfunction "5_5") (pintype "unspecified"))
      (node (ref "U4") (pin "33") (pinfunction "IO40_33") (pintype "unspecified"))
    )
    (net (code "9") (name "CTRL_IN1_OUT1") (class "Default")
      (node (ref "U10") (pin "13") (pinfunction "CONT1_13") (pintype "unspecified"))
      (node (ref "U10") (pin "5") (pinfunction "CONT2_5") (pintype "unspecified"))
      (node (ref "U4") (pin "10") (pinfunction "IO17_10") (pintype "unspecified"))
    )
    (net (code "10") (name "CTRL_IN1_OUT2") (class "Default")
      (node (ref "U12") (pin "13") (pinfunction "CONT1_13") (pintype "unspecified"))
      (node (ref "U12") (pin "5") (pinfunction "CONT2_5") (pintype "unspecified"))
      (node (ref "U4") (pin "11") (pinfunction "IO18_11") (pintype "unspecified"))
    )
    (net (code "11") (name "CTRL_IN2_OUT1") (class "Default")
      (node (ref "U10") (pin "12") (pinfunction "CONT4_12") (pintype "unspecified"))
      (node (ref "U10") (pin "6") (pinfunction "CONT3_6") (pintype "unspecified"))
      (node (ref "U4") (pin "23") (pinfunction "IO21_23") (pintype "unspecified"))
    )
    (net (code "12") (name "CTRL_IN2_OUT2") (class "Default")
      (node (ref "U12") (pin "12") (pinfunction "CONT4_12") (pintype "unspecified"))
      (node (ref "U12") (pin "6") (pinfunction "CONT3_6") (pintype "unspecified"))
      (node (ref "U4") (pin "28") (pinfunction "IO35_28") (pintype "unspecified"))
    )
    (net (code "13") (name "DOWN") (class "Default")
      (node (ref "H3") (pin "4") (pinfunction "4_4") (pintype "unspecified"))
      (node (ref "U4") (pin "5") (pinfunction "IO5_5") (pintype "unspecified"))
    )
    (net (code "14") (name "ENTER") (class "Default")
      (node (ref "H3") (pin "6") (pinfunction "6_6") (pintype "unspecified"))
      (node (ref "U4") (pin "15") (pinfunction "IO3_15") (pintype "unspecified"))
    )
    (net (code "15") (name "GND") (class "Default")
      (node (ref "C1") (pin "1") (pinfunction "1_1") (pintype "input"))
      (node (ref "C10") (pin "2") (pinfunction "2_2") (pintype "input"))
      (node (ref "C11") (pin "2") (pinfunction "2_2") (pintype "input"))
      (node (ref "C12") (pin "2") (pinfunction "2_2") (pintype "input"))
      (node (ref "C13") (pin "2") (pinfunction "2_2") (pintype "input"))
      (node (ref "C2") (pin "2") (pinfunction "2_2") (pintype "input"))
      (node (ref "C3") (pin "2") (pinfunction "2_2") (pintype "input"))
      (node (ref "C4") (pin "2") (pinfunction "2_2") (pintype "input"))
      (node (ref "C43") (pin "1") (pinfunction "1_1") (pintype "unspecified"))
      (node (ref "C44") (pin "1") (pinfunction "1_1") (pintype "unspecified"))
      (node (ref "C45") (pin "1") (pinfunction "1_1") (pintype "unspecified"))
      (node (ref "C46") (pin "2") (pinfunction "2_2") (pintype "unspecified"))
      (node (ref "C47") (pin "2") (pinfunction "2_2") (pintype "unspecified"))
      (node (ref "C5") (pin "2") (pinfunction "2_2") (pintype "input"))
      (node (ref "C6") (pin "2") (pinfunction "2_2") (pintype "input"))
      (node (ref "C7") (pin "2") (pinfunction "2_2") (pintype "input"))
      (node (ref "C8") (pin "2") (pinfunction "2_2") (pintype "input"))
      (node (ref "C9") (pin "2") (pinfunction "2_2") (pintype "input"))
      (node (ref "CN5") (pin "1") (pinfunction "1_1") (pintype "unspecified"))
      (node (ref "CN6") (pin "1") (pinfunction "1_1") (pintype "unspecified"))
      (node (ref "CN7") (pin "1") (pinfunction "1_1") (pintype "unspecified"))
      (node (ref "CN8") (pin "1") (pinfunction "1_1") (pintype "unspecified"))
      (node (ref "H1") (pin "2") (pinfunction "2_2") (pintype "unspecified"))
      (node (ref "H2") (pin "1") (pinfunction "1_1") (pintype "input"))
      (node (ref "H3") (pin "1") (pinfunction "1_1") (pintype "unspecified"))
      (node (ref "H4") (pin "2") (pinfunction "2_2") (pintype "unspecified"))
      (node (ref "H4") (pin "7") (pinfunction "7_7") (pintype "unspecified"))
      (node (ref "H5") (pin "2") (pinfunction "2_2") (pintype "unspecified"))
      (node (ref "H5") (pin "7") (pinfunction "7_7") (pintype "unspecified"))
      (node (ref "H6") (pin "2") (pinfunction "2_2") (pintype "unspecified"))
      (node (ref "H6") (pin "7") (pinfunction "7_7") (pintype "unspecified"))
      (node (ref "H7") (pin "2") (pinfunction "2_2") (pintype "unspecified"))
      (node (ref "H7") (pin "7") (pinfunction "7_7") (pintype "unspecified"))
      (node (ref "H8") (pin "2") (pinfunction "2_2") (pintype "unspecified"))
      (node (ref "H8") (pin "7") (pinfunction "7_7") (pintype "unspecified"))
      (node (ref "Q2") (pin "2") (pinfunction "E_2") (pintype "unspecified"))
      (node (ref "Q4") (pin "2") (pinfunction "E_2") (pintype "unspecified"))
      (node (ref "Q6") (pin "2") (pinfunction "E_2") (pintype "unspecified"))
      (node (ref "Q8") (pin "2") (pinfunction "E_2") (pintype "unspecified"))
      (node (ref "R1") (pin "1") (pinfunction "1_1") (pintype "input"))
      (node (ref "R11") (pin "1") (pinfunction "1_1") (pintype "input"))
      (node (ref "R14") (pin "1") (pinfunction "1_1") (pintype "input"))
      (node (ref "R2") (pin "1") (pinfunction "1_1") (pintype "input"))
      (node (ref "R4") (pin "1") (pinfunction "1_1") (pintype "input"))
      (node (ref "R40") (pin "1") (pinfunction "1_1") (pintype "unspecified"))
      (node (ref "R42") (pin "1") (pinfunction "1_1") (pintype "unspecified"))
      (node (ref "R44") (pin "1") (pinfunction "1_1") (pintype "unspecified"))
      (node (ref "R46") (pin "1") (pinfunction "1_1") (pintype "unspecified"))
      (node (ref "R5") (pin "1") (pinfunction "1_1") (pintype "input"))
      (node (ref "R50") (pin "1") (pinfunction "1_1") (pintype "input"))
      (node (ref "R52") (pin "1") (pinfunction "1_1") (pintype "unspecified"))
      (node (ref "R7") (pin "1") (pinfunction "1_1") (pintype "input"))
      (node (ref "R9") (pin "1") (pinfunction "1_1") (pintype "input"))
      (node (ref "TP6") (pin "1") (pinfunction "1_1") (pintype "unspecified"))
      (node (ref "U1") (pin "10") (pinfunction "VSS_10") (pintype "unspecified"))
      (node (ref "U1") (pin "11") (pinfunction "VSS_11") (pintype "unspecified"))
      (node (ref "U1") (pin "21") (pinfunction "EP_21") (pintype "unspecified"))
      (node (ref "U1") (pin "3") (pinfunction "SEL_3") (pintype "unspecified"))
      (node (ref "U10") (pin "7") (pinfunction "VSS_7") (pintype "unspecified"))
      (node (ref "U12") (pin "7") (pinfunction "VSS_7") (pintype "unspecified"))
      (node (ref "U2") (pin "11") (pinfunction "EP_11") (pintype "input"))
      (node (ref "U2") (pin "3") (pinfunction "PGND_3") (pintype "input"))
      (node (ref "U2") (pin "9") (pinfunction "GND_9") (pintype "input"))
      (node (ref "U3") (pin "11") (pinfunction "EP_11") (pintype "input"))
      (node (ref "U3") (pin "3") (pinfunction "PGND_3") (pintype "input"))
      (node (ref "U3") (pin "9") (pinfunction "GND_9") (pintype "input"))
      (node (ref "U4") (pin "1") (pinfunction "GND_1") (pintype "unspecified"))
      (node (ref "U4") (pin "40") (pinfunction "GND_40") (pintype "unspecified"))
      (node (ref "U4") (pin "41") (pinfunction "GND_41") (pintype "unspecified"))
      (node (ref "U6") (pin "12") (pinfunction "SHDN#_12") (pintype "unspecified"))
      (node (ref "U6") (pin "4") (pinfunction "VSS_4") (pintype "unspecified"))
      (node (ref "U6") (pin "7") (pinfunction "P1A_7") (pintype "unspecified"))
      (node (ref "U6") (pin "8") (pinfunction "P0A_8") (pintype "unspecified"))
      (node (ref "U7") (pin "12") (pinfunction "SHDN#_12") (pintype "unspecified"))
      (node (ref "U7") (pin "4") (pinfunction "VSS_4") (pintype "unspecified"))
      (node (ref "U7") (pin "7") (pinfunction "P1A_7") (pintype "unspecified"))
      (node (ref "U7") (pin "8") (pinfunction "P0A_8") (pintype "unspecified"))
      (node (ref "U8") (pin "11") (pinfunction "GND_11") (pintype "unspecified"))
      (node (ref "USB1") (pin "1") (pinfunction "GND_1") (pintype "unspecified"))
      (node (ref "USB1") (pin "12") (pinfunction "GND_12") (pintype "unspecified"))
      (node (ref "USB1") (pin "13") (pinfunction "SHELL_13") (pintype "unspecified"))
      (node (ref "USB1") (pin "14") (pinfunction "SHELL_14") (pintype "unspecified"))
    )
    (net (code "16") (name "IJACK1_L") (class "Default")
      (node (ref "C55") (pin "2") (pinfunction "2_2") (pintype "input"))
      (node (ref "CN5") (pin "5") (pinfunction "5_5") (pintype "unspecified"))
    )
    (net (code "17") (name "IJACK1_R") (class "Default")
      (node (ref "C54") (pin "2") (pinfunction "2_2") (pintype "input"))
      (node (ref "CN5") (pin "2") (pinfunction "2_2") (pintype "unspecified"))
    )
    (net (code "18") (name "IJACK2_L") (class "Default")
      (node (ref "C57") (pin "2") (pinfunction "2_2") (pintype "input"))
      (node (ref "CN6") (pin "5") (pinfunction "5_5") (pintype "unspecified"))
    )
    (net (code "19") (name "IJACK2_R") (class "Default")
      (node (ref "C56") (pin "2") (pinfunction "2_2") (pintype "input"))
      (node (ref "CN6") (pin "2") (pinfunction "2_2") (pintype "unspecified"))
    )
    (net (code "20") (name "IN1_L") (class "Default")
      (node (ref "C55") (pin "1") (pinfunction "1_1") (pintype "input"))
      (node (ref "R41") (pin "1") (pinfunction "1_1") (pintype "unspecified"))
      (node (ref "R42") (pin "2") (pinfunction "2_2") (pintype "unspecified"))
      (node (ref "U6") (pin "10") (pinfunction "P0B_10") (pintype "unspecified"))
    )
    (net (code "21") (name "IN1_L_SW1") (class "Default")
      (node (ref "R33") (pin "1") (pinfunction "1_1") (pintype "unspecified"))
      (node (ref "U10") (pin "3") (pinfunction "OUT/IN2_3") (pintype "unspecified"))
    )
    (net (code "22") (name "IN1_L_SW2") (class "Default")
      (node (ref "R32") (pin "1") (pinfunction "1_1") (pintype "unspecified"))
      (node (ref "U12") (pin "3") (pinfunction "OUT/IN2_3") (pintype "unspecified"))
    )
    (net (code "23") (name "IN1_POTOUT_L") (class "Default")
      (node (ref "U10") (pin "4") (pinfunction "IN/OUT2_4") (pintype "unspecified"))
      (node (ref "U12") (pin "4") (pinfunction "IN/OUT2_4") (pintype "unspecified"))
      (node (ref "U6") (pin "9") (pinfunction "P0W_9") (pintype "unspecified"))
    )
    (net (code "24") (name "IN1_POTOUT_R") (class "Default")
      (node (ref "U10") (pin "1") (pinfunction "IN/OUT1_1") (pintype "unspecified"))
      (node (ref "U12") (pin "1") (pinfunction "IN/OUT1_1") (pintype "unspecified"))
      (node (ref "U6") (pin "6") (pinfunction "P1W_6") (pintype "unspecified"))
    )
    (net (code "25") (name "IN1_R") (class "Default")
      (node (ref "C54") (pin "1") (pinfunction "1_1") (pintype "input"))
      (node (ref "R39") (pin "1") (pinfunction "1_1") (pintype "unspecified"))
      (node (ref "R40") (pin "2") (pinfunction "2_2") (pintype "unspecified"))
      (node (ref "U6") (pin "5") (pinfunction "P1B_5") (pintype "unspecified"))
    )
    (net (code "26") (name "IN1_R_SW1") (class "Default")
      (node (ref "R25") (pin "1") (pinfunction "1_1") (pintype "unspecified"))
      (node (ref "U10") (pin "2") (pinfunction "OUT/IN1_2") (pintype "unspecified"))
    )
    (net (code "27") (name "IN1_R_SW2") (class "Default")
      (node (ref "R28") (pin "1") (pinfunction "1_1") (pintype "unspecified"))
      (node (ref "U12") (pin "2") (pinfunction "OUT/IN1_2") (pintype "unspecified"))
    )
    (net (code "28") (name "IN2_L") (class "Default")
      (node (ref "C57") (pin "1") (pinfunction "1_1") (pintype "input"))
      (node (ref "R45") (pin "1") (pinfunction "1_1") (pintype "unspecified"))
      (node (ref "R46") (pin "2") (pinfunction "2_2") (pintype "unspecified"))
      (node (ref "U7") (pin "10") (pinfunction "P0B_10") (pintype "unspecified"))
    )
    (net (code "29") (name "IN2_L_SW1") (class "Default")
      (node (ref "R34") (pin "1") (pinfunction "1_1") (pintype "unspecified"))
      (node (ref "U10") (pin "9") (pinfunction "OUT/IN3_9") (pintype "unspecified"))
    )
    (net (code "30") (name "IN2_L_SW2") (class "Default")
      (node (ref "R31") (pin "1") (pinfunction "1_1") (pintype "unspecified"))
      (node (ref "U12") (pin "9") (pinfunction "OUT/IN3_9") (pintype "unspecified"))
    )
    (net (code "31") (name "IN2_POTOUT_L") (class "Default")
      (node (ref "U10") (pin "8") (pinfunction "IN/OUT3_8") (pintype "unspecified"))
      (node (ref "U12") (pin "8") (pinfunction "IN/OUT3_8") (pintype "unspecified"))
      (node (ref "U7") (pin "9") (pinfunction "P0W_9") (pintype "unspecified"))
    )
    (net (code "32") (name "IN2_POTOUT_R") (class "Default")
      (node (ref "U10") (pin "11") (pinfunction "IN/OUT4_11") (pintype "unspecified"))
      (node (ref "U12") (pin "11") (pinfunction "IN/OUT4_11") (pintype "unspecified"))
      (node (ref "U7") (pin "6") (pinfunction "P1W_6") (pintype "unspecified"))
    )
    (net (code "33") (name "IN2_R") (class "Default")
      (node (ref "C56") (pin "1") (pinfunction "1_1") (pintype "input"))
      (node (ref "R43") (pin "1") (pinfunction "1_1") (pintype "unspecified"))
      (node (ref "R44") (pin "2") (pinfunction "2_2") (pintype "unspecified"))
      (node (ref "U7") (pin "5") (pinfunction "P1B_5") (pintype "unspecified"))
    )
    (net (code "34") (name "IN2_R_SW1") (class "Default")
      (node (ref "R26") (pin "1") (pinfunction "1_1") (pintype "unspecified"))
      (node (ref "U10") (pin "10") (pinfunction "OUT/IN4_10") (pintype "unspecified"))
    )
    (net (code "35") (name "IN2_R_SW2") (class "Default")
      (node (ref "R27") (pin "1") (pinfunction "1_1") (pintype "unspecified"))
      (node (ref "U12") (pin "10") (pinfunction "OUT/IN4_10") (pintype "unspecified"))
    )
    (net (code "36") (name "LEFT") (class "Default")
      (node (ref "H3") (pin "2") (pinfunction "2_2") (pintype "unspecified"))
      (node (ref "U4") (pin "7") (pinfunction "IO7_7") (pintype "unspecified"))
    )
    (net (code "37") (name "MISO") (class "Default")
      (node (ref "H4") (pin "4") (pinfunction "4_4") (pintype "unspecified"))
      (node (ref "H5") (pin "4") (pinfunction "4_4") (pintype "unspecified"))
      (node (ref "H6") (pin "4") (pinfunction "4_4") (pintype "unspecified"))
      (node (ref "H7") (pin "4") (pinfunction "4_4") (pintype "unspecified"))
      (node (ref "H8") (pin "4") (pinfunction "4_4") (pintype "unspecified"))
      (node (ref "U4") (pin "20") (pinfunction "IO12_20") (pintype "unspecified"))
      (node (ref "U6") (pin "13") (pinfunction "SDO_13") (pintype "unspecified"))
      (node (ref "U7") (pin "13") (pinfunction "SDO_13") (pintype "unspecified"))
    )
    (net (code "38") (name "MOSI") (class "Default")
      (node (ref "H4") (pin "3") (pinfunction "3_3") (pintype "unspecified"))
      (node (ref "H5") (pin "3") (pinfunction "3_3") (pintype "unspecified"))
      (node (ref "H6") (pin "3") (pinfunction "3_3") (pintype "unspecified"))
      (node (ref "H7") (pin "3") (pinfunction "3_3") (pintype "unspecified"))
      (node (ref "H8") (pin "3") (pinfunction "3_3") (pintype "unspecified"))
      (node (ref "U4") (pin "21") (pinfunction "IO13_21") (pintype "unspecified"))
      (node (ref "U6") (pin "3") (pinfunction "SDI_3") (pintype "unspecified"))
      (node (ref "U7") (pin "3") (pinfunction "SDI_3") (pintype "unspecified"))
    )
    (net (code "39") (name "Net-(Q1-B)") (class "Default")
      (node (ref "Q1") (pin "1") (pinfunction "B_1") (pintype "input"))
      (node (ref "Q2") (pin "1") (pinfunction "B_1") (pintype "unspecified"))
      (node (ref "U8") (pin "1") (pinfunction "OUT_1") (pintype "output"))
    )
    (net (code "40") (name "Net-(Q3-B)") (class "Default")
      (node (ref "Q3") (pin "1") (pinfunction "B_1") (pintype "input"))
      (node (ref "Q4") (pin "1") (pinfunction "B_1") (pintype "unspecified"))
      (node (ref "U8") (pin "7") (pinfunction "2OUT_7") (pintype "output"))
    )
    (net (code "41") (name "Net-(Q5-B)") (class "Default")
      (node (ref "Q5") (pin "1") (pinfunction "B_1") (pintype "input"))
      (node (ref "Q6") (pin "1") (pinfunction "B_1") (pintype "unspecified"))
      (node (ref "U8") (pin "8") (pinfunction "3OUT_8") (pintype "output"))
    )
    (net (code "42") (name "Net-(Q7-B)") (class "Default")
      (node (ref "Q7") (pin "1") (pinfunction "B_1") (pintype "input"))
      (node (ref "Q8") (pin "1") (pinfunction "B_1") (pintype "unspecified"))
      (node (ref "U8") (pin "14") (pinfunction "4OUT_14") (pintype "output"))
    )
    (net (code "43") (name "Net-(R14-Pad2)") (class "Default")
      (node (ref "R14") (pin "2") (pinfunction "2_2") (pintype "input"))
      (node (ref "R15") (pin "1") (pinfunction "1_1") (pintype "input"))
    )
    (net (code "44") (name "Net-(U1-PROG1)") (class "Default")
      (node (ref "R15") (pin "2") (pinfunction "2_2") (pintype "input"))
      (node (ref "U1") (pin "13") (pinfunction "PROG1_13") (pintype "unspecified"))
    )
    (net (code "45") (name "Net-(U1-PROG3)") (class "Default")
      (node (ref "R7") (pin "2") (pinfunction "2_2") (pintype "input"))
      (node (ref "U1") (pin "12") (pinfunction "PROG3_12") (pintype "unspecified"))
    )
    (net (code "46") (name "Net-(U1-THERM)") (class "Default")
      (node (ref "R5") (pin "2") (pinfunction "2_2") (pintype "input"))
      (node (ref "U1") (pin "5") (pinfunction "THERM_5") (pintype "unspecified"))
    )
    (net (code "47") (name "Net-(U1-VPCC)") (class "Default")
      (node (ref "R3") (pin "1") (pinfunction "1_1") (pintype "input"))
      (node (ref "R4") (pin "2") (pinfunction "2_2") (pintype "input"))
      (node (ref "U1") (pin "2") (pinfunction "VPCC_2") (pintype "unspecified"))
    )
    (net (code "48") (name "Net-(U2-EN)") (class "Default")
      (node (ref "C5") (pin "1") (pinfunction "1_1") (pintype "input"))
      (node (ref "U2") (pin "6") (pinfunction "EN_6") (pintype "input"))
      (node (ref "U2") (pin "7") (pinfunction "PS/SYNC_7") (pintype "input"))
      (node (ref "U2") (pin "8") (pinfunction "VINA_8") (pintype "input"))
    )
    (net (code "49") (name "Net-(U2-FB)") (class "Default")
      (node (ref "R8") (pin "1") (pinfunction "1_1") (pintype "input"))
      (node (ref "R9") (pin "2") (pinfunction "2_2") (pintype "input"))
      (node (ref "U2") (pin "10") (pinfunction "FB_10") (pintype "input"))
    )
    (net (code "50") (name "Net-(U2-L1)") (class "Default")
      (node (ref "L1") (pin "1") (pinfunction "1_1") (pintype "input"))
      (node (ref "U2") (pin "4") (pinfunction "L1_4") (pintype "input"))
    )
    (net (code "51") (name "Net-(U2-L2)") (class "Default")
      (node (ref "L1") (pin "2") (pinfunction "2_2") (pintype "input"))
      (node (ref "U2") (pin "2") (pinfunction "L2_2") (pintype "input"))
    )
    (net (code "52") (name "Net-(U3-EN)") (class "Default")
      (node (ref "C9") (pin "1") (pinfunction "1_1") (pintype "input"))
      (node (ref "U3") (pin "6") (pinfunction "EN_6") (pintype "input"))
      (node (ref "U3") (pin "7") (pinfunction "PS/SYNC_7") (pintype "input"))
      (node (ref "U3") (pin "8") (pinfunction "VINA_8") (pintype "input"))
    )
    (net (code "53") (name "Net-(U3-FB)") (class "Default")
      (node (ref "R10") (pin "1") (pinfunction "1_1") (pintype "input"))
      (node (ref "R11") (pin "2") (pinfunction "2_2") (pintype "input"))
      (node (ref "U3") (pin "10") (pinfunction "FB_10") (pintype "input"))
    )
    (net (code "54") (name "Net-(U3-L1)") (class "Default")
      (node (ref "L2") (pin "1") (pinfunction "1_1") (pintype "input"))
      (node (ref "U3") (pin "4") (pinfunction "L1_4") (pintype "input"))
    )
    (net (code "55") (name "Net-(U3-L2)") (class "Default")
      (node (ref "L2") (pin "2") (pinfunction "2_2") (pintype "input"))
      (node (ref "U3") (pin "2") (pinfunction "L2_2") (pintype "input"))
    )
    (net (code "56") (name "Net-(U4-EN)") (class "Default")
      (node (ref "R12") (pin "1") (pinfunction "1_1") (pintype "input"))
      (node (ref "TP1") (pin "1") (pinfunction "1_1") (pintype "unspecified"))
      (node (ref "U4") (pin "3") (pinfunction "EN_3") (pintype "unspecified"))
    )
    (net (code "57") (name "Net-(U4-IO0)") (class "Default")
      (node (ref "TP2") (pin "1") (pinfunction "1_1") (pintype "unspecified"))
      (node (ref "U4") (pin "27") (pinfunction "IO0_27") (pintype "unspecified"))
    )
    (net (code "58") (name "Net-(U4-RXD0)") (class "Default")
      (node (ref "TP4") (pin "1") (pinfunction "1_1") (pintype "unspecified"))
      (node (ref "U4") (pin "36") (pinfunction "RXD0_36") (pintype "unspecified"))
    )
    (net (code "59") (name "Net-(U4-TXD0)") (class "Default")
      (node (ref "TP3") (pin "1") (pinfunction "1_1") (pintype "unspecified"))
      (node (ref "U4") (pin "37") (pinfunction "TXD0_37") (pintype "unspecified"))
    )
    (net (code "60") (name "Net-(U8A-1IN-)") (class "Default")
      (node (ref "R23") (pin "1") (pinfunction "1_1") (pintype "unspecified"))
      (node (ref "R33") (pin "2") (pinfunction "2_2") (pintype "unspecified"))
      (node (ref "R34") (pin "2") (pinfunction "2_2") (pintype "unspecified"))
      (node (ref "U8") (pin "2") (pinfunction "1IN-_2") (pintype "unspecified"))
    )
    (net (code "61") (name "Net-(U8B-2IN-)") (class "Default")
      (node (ref "R24") (pin "1") (pinfunction "1_1") (pintype "unspecified"))
      (node (ref "R25") (pin "2") (pinfunction "2_2") (pintype "unspecified"))
      (node (ref "R26") (pin "2") (pinfunction "2_2") (pintype "unspecified"))
      (node (ref "U8") (pin "6") (pinfunction "2IN-_6") (pintype "unspecified"))
    )
    (net (code "62") (name "Net-(U8C-3IN-)") (class "Default")
      (node (ref "R30") (pin "1") (pinfunction "1_1") (pintype "unspecified"))
      (node (ref "R31") (pin "2") (pinfunction "2_2") (pintype "unspecified"))
      (node (ref "R32") (pin "2") (pinfunction "2_2") (pintype "unspecified"))
      (node (ref "U8") (pin "9") (pinfunction "3IN-_9") (pintype "unspecified"))
    )
    (net (code "63") (name "Net-(U8D-4IN-)") (class "Default")
      (node (ref "R27") (pin "2") (pinfunction "2_2") (pintype "unspecified"))
      (node (ref "R28") (pin "2") (pinfunction "2_2") (pintype "unspecified"))
      (node (ref "R29") (pin "1") (pinfunction "1_1") (pintype "unspecified"))
      (node (ref "U8") (pin "13") (pinfunction "4IN-_13") (pintype "unspecified"))
    )
    (net (code "64") (name "Net-(USB1-CC1)") (class "Default")
      (node (ref "R1") (pin "2") (pinfunction "2_2") (pintype "input"))
      (node (ref "USB1") (pin "4") (pinfunction "CC1_4") (pintype "unspecified"))
    )
    (net (code "65") (name "Net-(USB1-CC2)") (class "Default")
      (node (ref "R2") (pin "2") (pinfunction "2_2") (pintype "input"))
      (node (ref "USB1") (pin "10") (pinfunction "CC2_10") (pintype "unspecified"))
    )
    (net (code "66") (name "OJACK1_L") (class "Default")
      (node (ref "C48") (pin "1") (pinfunction "1_1") (pintype "input"))
      (node (ref "CN7") (pin "5") (pinfunction "5_5") (pintype "unspecified"))
    )
    (net (code "67") (name "OJACK1_R") (class "Default")
      (node (ref "C49") (pin "1") (pinfunction "1_1") (pintype "input"))
      (node (ref "CN7") (pin "2") (pinfunction "2_2") (pintype "unspecified"))
    )
    (net (code "68") (name "OJACK2_L") (class "Default")
      (node (ref "C51") (pin "1") (pinfunction "1_1") (pintype "input"))
      (node (ref "CN8") (pin "5") (pinfunction "5_5") (pintype "unspecified"))
    )
    (net (code "69") (name "OJACK2_R") (class "Default")
      (node (ref "C50") (pin "1") (pinfunction "1_1") (pintype "input"))
      (node (ref "CN8") (pin "2") (pinfunction "2_2") (pintype "unspecified"))
    )
    (net (code "70") (name "OUT1_L") (class "Default")
      (node (ref "C48") (pin "2") (pinfunction "2_2") (pintype "input"))
      (node (ref "Q1") (pin "2") (pinfunction "E_2") (pintype "input"))
      (node (ref "Q2") (pin "3") (pinfunction "C_3") (pintype "unspecified"))
      (node (ref "R23") (pin "2") (pinfunction "2_2") (pintype "unspecified"))
    )
    (net (code "71") (name "OUT1_R") (class "Default")
      (node (ref "C49") (pin "2") (pinfunction "2_2") (pintype "input"))
      (node (ref "Q3") (pin "2") (pinfunction "E_2") (pintype "input"))
      (node (ref "Q4") (pin "3") (pinfunction "C_3") (pintype "unspecified"))
      (node (ref "R24") (pin "2") (pinfunction "2_2") (pintype "unspecified"))
    )
    (net (code "72") (name "OUT2_L") (class "Default")
      (node (ref "C51") (pin "2") (pinfunction "2_2") (pintype "input"))
      (node (ref "Q5") (pin "2") (pinfunction "E_2") (pintype "input"))
      (node (ref "Q6") (pin "3") (pinfunction "C_3") (pintype "unspecified"))
      (node (ref "R30") (pin "2") (pinfunction "2_2") (pintype "unspecified"))
    )
    (net (code "73") (name "OUT2_R") (class "Default")
      (node (ref "C50") (pin "2") (pinfunction "2_2") (pintype "input"))
      (node (ref "Q7") (pin "2") (pinfunction "E_2") (pintype "input"))
      (node (ref "Q8") (pin "3") (pinfunction "C_3") (pintype "unspecified"))
      (node (ref "R29") (pin "2") (pinfunction "2_2") (pintype "unspecified"))
    )
    (net (code "74") (name "P1_CS") (class "Default")
      (node (ref "U4") (pin "8") (pinfunction "IO15_8") (pintype "unspecified"))
      (node (ref "U6") (pin "1") (pinfunction "CS#_1") (pintype "unspecified"))
    )
    (net (code "75") (name "P2_CS") (class "Default")
      (node (ref "U4") (pin "9") (pinfunction "IO16_9") (pintype "unspecified"))
      (node (ref "U7") (pin "1") (pinfunction "CS#_1") (pintype "unspecified"))
    )
    (net (code "76") (name "REF_1V65") (class "Default")
      (node (ref "R51") (pin "1") (pinfunction "1_1") (pintype "unspecified"))
      (node (ref "R52") (pin "2") (pinfunction "2_2") (pintype "unspecified"))
      (node (ref "U8") (pin "10") (pinfunction "3IN+_10") (pintype "unspecified"))
      (node (ref "U8") (pin "12") (pinfunction "4IN+_12") (pintype "unspecified"))
      (node (ref "U8") (pin "3") (pinfunction "1IN+_3") (pintype "unspecified"))
      (node (ref "U8") (pin "5") (pinfunction "2IN+_5") (pintype "unspecified"))
    )
    (net (code "77") (name "RIGHT") (class "Default")
      (node (ref "H3") (pin "3") (pinfunction "3_3") (pintype "unspecified"))
      (node (ref "U4") (pin "6") (pinfunction "IO6_6") (pintype "unspecified"))
    )
    (net (code "78") (name "SCL") (class "Default")
      (node (ref "H2") (pin "4") (pinfunction "4_4") (pintype "input"))
      (node (ref "U4") (pin "17") (pinfunction "IO9_17") (pintype "unspecified"))
    )
    (net (code "79") (name "SDA") (class "Default")
      (node (ref "H2") (pin "3") (pinfunction "3_3") (pintype "input"))
      (node (ref "U4") (pin "12") (pinfunction "IO8_12") (pintype "unspecified"))
    )
    (net (code "80") (name "UP") (class "Default")
      (node (ref "H3") (pin "5") (pinfunction "5_5") (pintype "unspecified"))
      (node (ref "U4") (pin "4") (pinfunction "IO4_4") (pintype "unspecified"))
    )
    (net (code "81") (name "USB_DM") (class "Default")
      (node (ref "U4") (pin "13") (pinfunction "IO19_13") (pintype "unspecified"))
      (node (ref "USB1") (pin "5") (pinfunction "DN2_5") (pintype "unspecified"))
      (node (ref "USB1") (pin "7") (pinfunction "DN1_7") (pintype "unspecified"))
    )
    (net (code "82") (name "USB_DP") (class "Default")
      (node (ref "U4") (pin "14") (pinfunction "IO20_14") (pintype "unspecified"))
      (node (ref "USB1") (pin "6") (pinfunction "DP1_6") (pintype "unspecified"))
      (node (ref "USB1") (pin "8") (pinfunction "DP2_8") (pintype "unspecified"))
    )
    (net (code "83") (name "USB_SENSE") (class "Default")
      (node (ref "U1") (pin "6") (pinfunction "PG#_6") (pintype "unspecified"))
      (node (ref "U4") (pin "38") (pinfunction "IO2_38") (pintype "unspecified"))
    )
    (net (code "84") (name "VBAT") (class "Default")
      (node (ref "C3") (pin "1") (pinfunction "1_1") (pintype "input"))
      (node (ref "H1") (pin "1") (pinfunction "1_1") (pintype "unspecified"))
      (node (ref "R49") (pin "2") (pinfunction "2_2") (pintype "input"))
      (node (ref "U1") (pin "14") (pinfunction "VBAT_14") (pintype "unspecified"))
      (node (ref "U1") (pin "15") (pinfunction "VBAT_15") (pintype "unspecified"))
      (node (ref "U1") (pin "16") (pinfunction "VBAT_SENSE_16") (pintype "unspecified"))
    )
    (net (code "85") (name "VBAT_SENSE") (class "Default")
      (node (ref "R49") (pin "1") (pinfunction "1_1") (pintype "input"))
      (node (ref "R50") (pin "2") (pinfunction "2_2") (pintype "input"))
      (node (ref "U4") (pin "39") (pinfunction "IO1_39") (pintype "unspecified"))
    )
    (net (code "86") (name "VBUS") (class "Default")
      (node (ref "C1") (pin "2") (pinfunction "2_2") (pintype "input"))
      (node (ref "R3") (pin "2") (pinfunction "2_2") (pintype "input"))
      (node (ref "U1") (pin "18") (pinfunction "IN_18") (pintype "unspecified"))
      (node (ref "U1") (pin "19") (pinfunction "IN_19") (pintype "unspecified"))
      (node (ref "USB1") (pin "11") (pinfunction "VBUS_11") (pintype "unspecified"))
      (node (ref "USB1") (pin "2") (pinfunction "VBUS_2") (pintype "unspecified"))
    )
    (net (code "87") (name "VSYS") (class "Default")
      (node (ref "C2") (pin "1") (pinfunction "1_1") (pintype "input"))
      (node (ref "C4") (pin "1") (pinfunction "1_1") (pintype "input"))
      (node (ref "C8") (pin "1") (pinfunction "1_1") (pintype "input"))
      (node (ref "U1") (pin "1") (pinfunction "OUT_1") (pintype "unspecified"))
      (node (ref "U1") (pin "17") (pinfunction "CE_17") (pintype "unspecified"))
      (node (ref "U1") (pin "20") (pinfunction "OUT_20") (pintype "unspecified"))
      (node (ref "U1") (pin "4") (pinfunction "PROG2_4") (pintype "unspecified"))
      (node (ref "U1") (pin "9") (pinfunction "TE#_9") (pintype "unspecified"))
      (node (ref "U2") (pin "5") (pinfunction "VIN_5") (pintype "input"))
      (node (ref "U3") (pin "5") (pinfunction "VIN_5") (pintype "input"))
    )
    (net (code "88") (name "unconnected-(CN5-Pad3)") (class "Default")
      (node (ref "CN5") (pin "3") (pinfunction "3_3") (pintype "unspecified"))
    )
    (net (code "89") (name "unconnected-(CN5-Pad4)") (class "Default")
      (node (ref "CN5") (pin "4") (pinfunction "4_4") (pintype "unspecified"))
    )
    (net (code "90") (name "unconnected-(CN6-Pad3)") (class "Default")
      (node (ref "CN6") (pin "3") (pinfunction "3_3") (pintype "unspecified"))
    )
    (net (code "91") (name "unconnected-(CN6-Pad4)") (class "Default")
      (node (ref "CN6") (pin "4") (pinfunction "4_4") (pintype "unspecified"))
    )
    (net (code "92") (name "unconnected-(CN7-Pad3)") (class "Default")
      (node (ref "CN7") (pin "3") (pinfunction "3_3") (pintype "unspecified"))
    )
    (net (code "93") (name "unconnected-(CN7-Pad4)") (class "Default")
      (node (ref "CN7") (pin "4") (pinfunction "4_4") (pintype "unspecified"))
    )
    (net (code "94") (name "unconnected-(CN8-Pad3)") (class "Default")
      (node (ref "CN8") (pin "3") (pinfunction "3_3") (pintype "unspecified"))
    )
    (net (code "95") (name "unconnected-(CN8-Pad4)") (class "Default")
      (node (ref "CN8") (pin "4") (pinfunction "4_4") (pintype "unspecified"))
    )
    (net (code "96") (name "unconnected-(U1-STAT1{slash}LBO#-Pad8)") (class "Default")
      (node (ref "U1") (pin "8") (pinfunction "STAT1/LBO#_8") (pintype "unspecified"))
    )
    (net (code "97") (name "unconnected-(U1-STAT2-Pad7)") (class "Default")
      (node (ref "U1") (pin "7") (pinfunction "STAT2_7") (pintype "unspecified"))
    )
    (net (code "98") (name "unconnected-(U4-IO10-Pad18)") (class "Default")
      (node (ref "U4") (pin "18") (pinfunction "IO10_18") (pintype "unspecified"))
    )
    (net (code "99") (name "unconnected-(U4-IO11-Pad19)") (class "Default")
      (node (ref "U4") (pin "19") (pinfunction "IO11_19") (pintype "unspecified"))
    )
    (net (code "100") (name "unconnected-(U4-IO41-Pad34)") (class "Default")
      (node (ref "U4") (pin "34") (pinfunction "IO41_34") (pintype "unspecified"))
    )
    (net (code "101") (name "unconnected-(U4-IO42-Pad35)") (class "Default")
      (node (ref "U4") (pin "35") (pinfunction "IO42_35") (pintype "unspecified"))
    )
    (net (code "102") (name "unconnected-(U4-IO45-Pad26)") (class "Default")
      (node (ref "U4") (pin "26") (pinfunction "IO45_26") (pintype "unspecified"))
    )
    (net (code "103") (name "unconnected-(U4-IO46-Pad16)") (class "Default")
      (node (ref "U4") (pin "16") (pinfunction "IO46_16") (pintype "unspecified"))
    )
    (net (code "104") (name "unconnected-(U4-IO47-Pad24)") (class "Default")
      (node (ref "U4") (pin "24") (pinfunction "IO47_24") (pintype "unspecified"))
    )
    (net (code "105") (name "unconnected-(U4-IO48-Pad25)") (class "Default")
      (node (ref "U4") (pin "25") (pinfunction "IO48_25") (pintype "unspecified"))
    )
    (net (code "106") (name "unconnected-(U6-WP#-Pad11)") (class "Default")
      (node (ref "U6") (pin "11") (pinfunction "WP#_11") (pintype "unspecified"))
    )
    (net (code "107") (name "unconnected-(U7-WP#-Pad11)") (class "Default")
      (node (ref "U7") (pin "11") (pinfunction "WP#_11") (pintype "unspecified"))
    )
    (net (code "108") (name "unconnected-(USB1-SBU1-Pad9)") (class "Default")
      (node (ref "USB1") (pin "9") (pinfunction "SBU1_9") (pintype "unspecified"))
    )
    (net (code "109") (name "unconnected-(USB1-SBU2-Pad3)") (class "Default")
      (node (ref "USB1") (pin "3") (pinfunction "SBU2_3") (pintype "unspecified"))
    )
  )
)
